# 10_FPGA_misc.net
KiCad netlist of a schematic drawn in Altium Designer
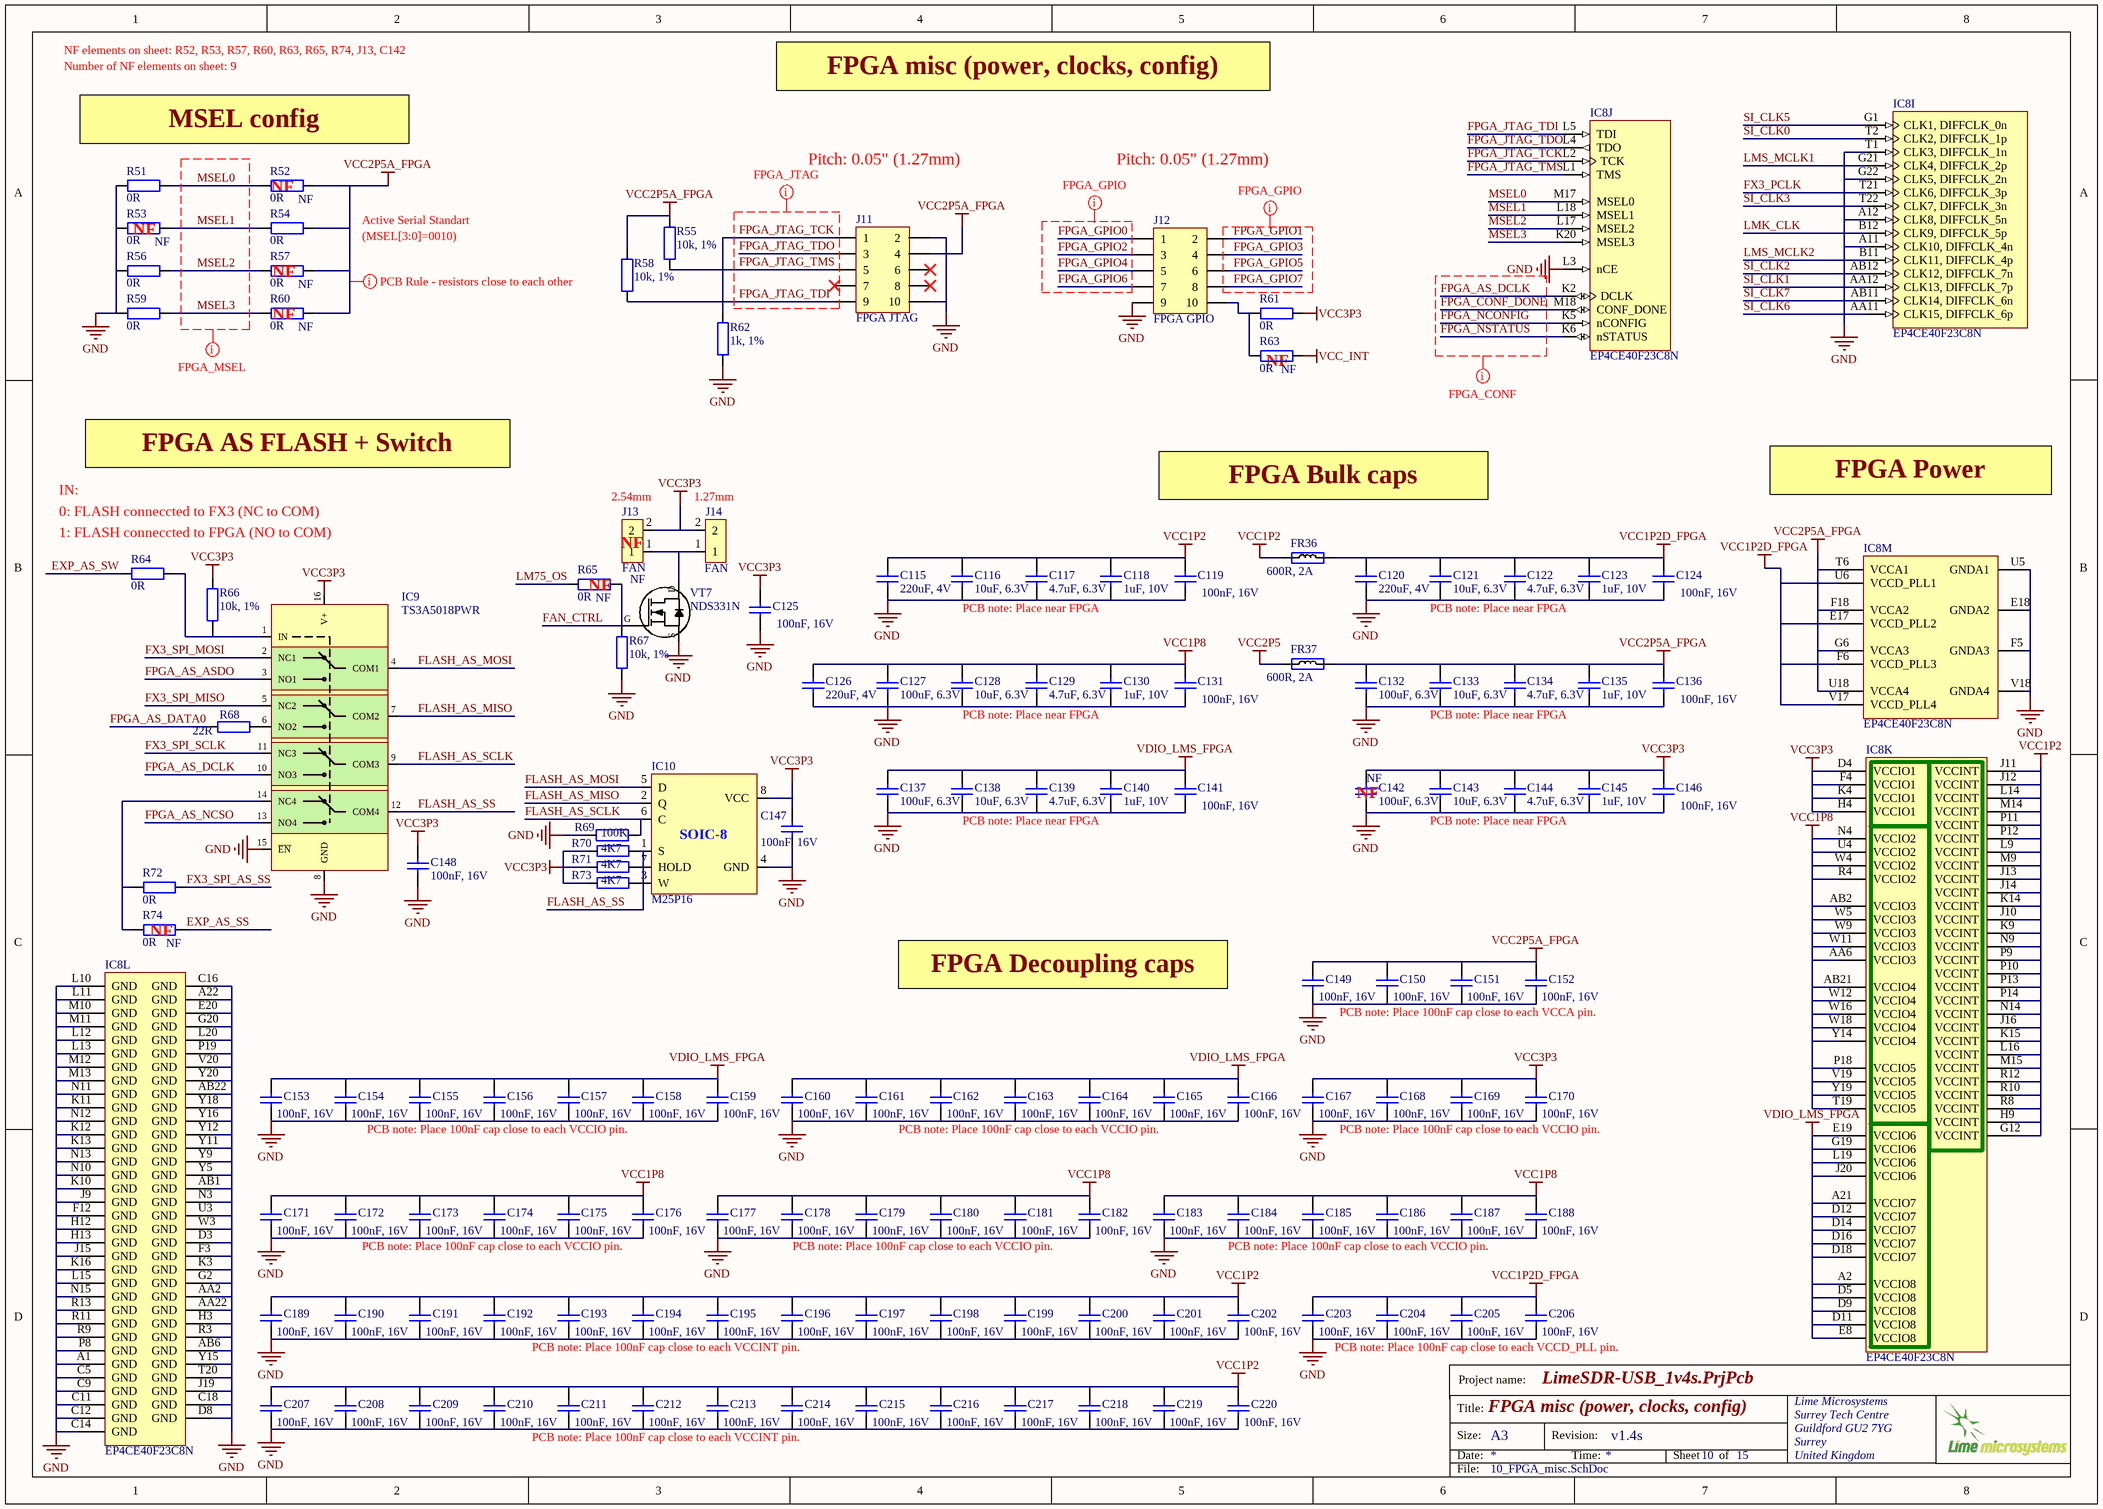
[diagram p0: 10_FPGA_misc.SchDoc]

(export (version "E")
  (design (tool "Eeschema 10.0.6"))
  (components
    (comp (ref "C115")
      (value "220uF, 4V")
      (footprint "CAP1206")
      (fields
        (field (name "MANUFACTURER PART NUMBER") "GRM31CR60G227ME11L")
        (field (name "MANUFACTURER") "Murata Electronics North America")
        (field (name "TOLERANCE") "±20%")
      )
      (libsource (lib "LimeFPGAboard_schLib") (part "Cap_1206"))
    )
    (comp (ref "C116")
      (value "10uF, 6.3V")
      (footprint "CAP0603")
      (fields (field (name "TOLERANCE") "±20%") (field (name "MANUFACTURER") "Yageo"))
      (libsource (lib "LimeFPGAboard_schLib") (part "Cap_0603"))
    )
    (comp (ref "C117")
      (value "4.7uF, 6.3V")
      (footprint "CAP0402")
      (fields
        (field (name "MANUFACTURER") "Murata Electronics North America")
        (field (name "TOLERANCE") "±20%")
        (field (name "MANUFACTURER PART NUMBER") "GRM155R60J475ME87D")
      )
      (libsource (lib "LimeMicroAltiumLib_schLib") (part "Cap_0402"))
    )
    (comp (ref "C118")
      (value "1uF, 10V")
      (footprint "CAP0402")
      (fields (field (name "MANUFACTURER") "TDK"))
      (libsource (lib "LimeMicroAltiumLib_schLib") (part "Cap_0402"))
    )
    (comp (ref "C119")
      (value "100nF, 16V")
      (footprint "CAP0402")
      (fields
        (field (name "TOLERANCE") "10 %")
        (field (name "MANUFACTURER") "Murata Electronics")
        (field (name "MANUFACTURER PART NUMBER") "GRM155R71C104KA88D")
      )
      (libsource (lib "LimeFPGAboard_schLib") (part "Cap_0603"))
    )
    (comp (ref "C120")
      (value "220uF, 4V")
      (footprint "CAP1206")
      (fields
        (field (name "MANUFACTURER PART NUMBER") "GRM31CR60G227ME11L")
        (field (name "MANUFACTURER") "Murata Electronics North America")
        (field (name "TOLERANCE") "±20%")
      )
      (libsource (lib "LimeFPGAboard_schLib") (part "Cap_1206"))
    )
    (comp (ref "C121")
      (value "10uF, 6.3V")
      (footprint "CAP0603")
      (fields (field (name "TOLERANCE") "±20%") (field (name "MANUFACTURER") "Yageo"))
      (libsource (lib "LimeFPGAboard_schLib") (part "Cap_0603"))
    )
    (comp (ref "C122")
      (value "4.7uF, 6.3V")
      (footprint "CAP0402")
      (fields
        (field (name "MANUFACTURER") "Murata Electronics North America")
        (field (name "TOLERANCE") "±20%")
        (field (name "MANUFACTURER PART NUMBER") "GRM155R60J475ME87D")
      )
      (libsource (lib "LimeMicroAltiumLib_schLib") (part "Cap_0402"))
    )
    (comp (ref "C123")
      (value "1uF, 10V")
      (footprint "CAP0402")
      (fields (field (name "MANUFACTURER") "TDK"))
      (libsource (lib "LimeMicroAltiumLib_schLib") (part "Cap_0402"))
    )
    (comp (ref "C124")
      (value "100nF, 16V")
      (footprint "CAP0402")
      (fields
        (field (name "TOLERANCE") "10 %")
        (field (name "MANUFACTURER") "Murata Electronics")
        (field (name "MANUFACTURER PART NUMBER") "GRM155R71C104KA88D")
      )
      (libsource (lib "LimeFPGAboard_schLib") (part "Cap_0603"))
    )
    (comp (ref "C125")
      (value "100nF, 16V")
      (footprint "CAP0402")
      (fields
        (field (name "TOLERANCE") "10 %")
        (field (name "MANUFACTURER") "Murata Electronics")
        (field (name "MANUFACTURER PART NUMBER") "GRM155R71C104KA88D")
      )
      (libsource (lib "LimeFPGAboard_schLib") (part "Cap_0603"))
    )
    (comp (ref "C126")
      (value "220uF, 4V")
      (footprint "CAP1206")
      (fields
        (field (name "MANUFACTURER PART NUMBER") "GRM31CR60G227ME11L")
        (field (name "MANUFACTURER") "Murata Electronics North America")
        (field (name "TOLERANCE") "±20%")
      )
      (libsource (lib "LimeFPGAboard_schLib") (part "Cap_1206"))
    )
    (comp (ref "C127")
      (value "100uF, 6.3V")
      (footprint "CAP1206")
      (fields (field (name "MANUFACTURER") "Murata Electronics North America"))
      (libsource (lib "LimeFPGAboard_schLib") (part "Cap_1206"))
    )
    (comp (ref "C128")
      (value "10uF, 6.3V")
      (footprint "CAP0603")
      (fields (field (name "TOLERANCE") "±20%") (field (name "MANUFACTURER") "Yageo"))
      (libsource (lib "LimeFPGAboard_schLib") (part "Cap_0603"))
    )
    (comp (ref "C129")
      (value "4.7uF, 6.3V")
      (footprint "CAP0402")
      (fields
        (field (name "MANUFACTURER") "Murata Electronics North America")
        (field (name "TOLERANCE") "±20%")
        (field (name "MANUFACTURER PART NUMBER") "GRM155R60J475ME87D")
      )
      (libsource (lib "LimeMicroAltiumLib_schLib") (part "Cap_0402"))
    )
    (comp (ref "C130")
      (value "1uF, 10V")
      (footprint "CAP0402")
      (fields (field (name "MANUFACTURER") "TDK"))
      (libsource (lib "LimeMicroAltiumLib_schLib") (part "Cap_0402"))
    )
    (comp (ref "C131")
      (value "100nF, 16V")
      (footprint "CAP0402")
      (fields
        (field (name "TOLERANCE") "10 %")
        (field (name "MANUFACTURER") "Murata Electronics")
        (field (name "MANUFACTURER PART NUMBER") "GRM155R71C104KA88D")
      )
      (libsource (lib "LimeFPGAboard_schLib") (part "Cap_0603"))
    )
    (comp (ref "C132")
      (value "100uF, 6.3V")
      (footprint "CAP1206")
      (fields (field (name "MANUFACTURER") "Murata Electronics North America"))
      (libsource (lib "LimeFPGAboard_schLib") (part "Cap_1206"))
    )
    (comp (ref "C133")
      (value "10uF, 6.3V")
      (footprint "CAP0603")
      (fields (field (name "TOLERANCE") "±20%") (field (name "MANUFACTURER") "Yageo"))
      (libsource (lib "LimeFPGAboard_schLib") (part "Cap_0603"))
    )
    (comp (ref "C134")
      (value "4.7uF, 6.3V")
      (footprint "CAP0402")
      (fields
        (field (name "MANUFACTURER") "Murata Electronics North America")
        (field (name "TOLERANCE") "±20%")
        (field (name "MANUFACTURER PART NUMBER") "GRM155R60J475ME87D")
      )
      (libsource (lib "LimeMicroAltiumLib_schLib") (part "Cap_0402"))
    )
    (comp (ref "C135")
      (value "1uF, 10V")
      (footprint "CAP0402")
      (fields (field (name "MANUFACTURER") "TDK"))
      (libsource (lib "LimeMicroAltiumLib_schLib") (part "Cap_0402"))
    )
    (comp (ref "C136")
      (value "100nF, 16V")
      (footprint "CAP0402")
      (fields
        (field (name "TOLERANCE") "10 %")
        (field (name "MANUFACTURER") "Murata Electronics")
        (field (name "MANUFACTURER PART NUMBER") "GRM155R71C104KA88D")
      )
      (libsource (lib "LimeFPGAboard_schLib") (part "Cap_0603"))
    )
    (comp (ref "C137")
      (value "100uF, 6.3V")
      (footprint "CAP1206")
      (fields (field (name "MANUFACTURER") "Murata Electronics North America"))
      (libsource (lib "LimeFPGAboard_schLib") (part "Cap_1206"))
    )
    (comp (ref "C138")
      (value "10uF, 6.3V")
      (footprint "CAP0603")
      (fields (field (name "TOLERANCE") "±20%") (field (name "MANUFACTURER") "Yageo"))
      (libsource (lib "LimeFPGAboard_schLib") (part "Cap_0603"))
    )
    (comp (ref "C139")
      (value "4.7uF, 6.3V")
      (footprint "CAP0402")
      (fields
        (field (name "MANUFACTURER") "Murata Electronics North America")
        (field (name "TOLERANCE") "±20%")
        (field (name "MANUFACTURER PART NUMBER") "GRM155R60J475ME87D")
      )
      (libsource (lib "LimeMicroAltiumLib_schLib") (part "Cap_0402"))
    )
    (comp (ref "C140")
      (value "1uF, 10V")
      (footprint "CAP0402")
      (fields (field (name "MANUFACTURER") "TDK"))
      (libsource (lib "LimeMicroAltiumLib_schLib") (part "Cap_0402"))
    )
    (comp (ref "C141")
      (value "100nF, 16V")
      (footprint "CAP0402")
      (fields
        (field (name "TOLERANCE") "10 %")
        (field (name "MANUFACTURER") "Murata Electronics")
        (field (name "MANUFACTURER PART NUMBER") "GRM155R71C104KA88D")
      )
      (libsource (lib "LimeFPGAboard_schLib") (part "Cap_0603"))
    )
    (comp (ref "C142")
      (value "100uF, 6.3V")
      (footprint "CAP1206")
      (fields
        (field (name "MANUFACTURER") "Murata Electronics North America")
        (field (name "ASSEMBLY INFO") "NF")
      )
      (libsource (lib "LimeFPGAboard_schLib") (part "Cap_1206"))
    )
    (comp (ref "C143")
      (value "10uF, 6.3V")
      (footprint "CAP0603")
      (fields (field (name "TOLERANCE") "±20%") (field (name "MANUFACTURER") "Yageo"))
      (libsource (lib "LimeFPGAboard_schLib") (part "Cap_0603"))
    )
    (comp (ref "C144")
      (value "4.7uF, 6.3V")
      (footprint "CAP0402")
      (fields
        (field (name "MANUFACTURER") "Murata Electronics North America")
        (field (name "TOLERANCE") "±20%")
        (field (name "MANUFACTURER PART NUMBER") "GRM155R60J475ME87D")
      )
      (libsource (lib "LimeMicroAltiumLib_schLib") (part "Cap_0402"))
    )
    (comp (ref "C145")
      (value "1uF, 10V")
      (footprint "CAP0402")
      (fields (field (name "MANUFACTURER") "TDK"))
      (libsource (lib "LimeMicroAltiumLib_schLib") (part "Cap_0402"))
    )
    (comp (ref "C146")
      (value "100nF, 16V")
      (footprint "CAP0402")
      (fields
        (field (name "TOLERANCE") "10 %")
        (field (name "MANUFACTURER") "Murata Electronics")
        (field (name "MANUFACTURER PART NUMBER") "GRM155R71C104KA88D")
      )
      (libsource (lib "LimeFPGAboard_schLib") (part "Cap_0603"))
    )
    (comp (ref "C147")
      (value "100nF, 16V")
      (footprint "CAP0402")
      (fields
        (field (name "TOLERANCE") "10 %")
        (field (name "MANUFACTURER") "Murata Electronics")
        (field (name "MANUFACTURER PART NUMBER") "GRM155R71C104KA88D")
      )
      (libsource (lib "LimeFPGAboard_schLib") (part "Cap_0603"))
    )
    (comp (ref "C148")
      (value "100nF, 16V")
      (footprint "CAP0402")
      (fields
        (field (name "TOLERANCE") "10 %")
        (field (name "MANUFACTURER") "Murata Electronics")
        (field (name "MANUFACTURER PART NUMBER") "GRM155R71C104KA88D")
      )
      (libsource (lib "LimeFPGAboard_schLib") (part "Cap_0603"))
    )
    (comp (ref "C149")
      (value "100nF, 16V")
      (footprint "CAP0402")
      (fields
        (field (name "TOLERANCE") "10 %")
        (field (name "MANUFACTURER") "Murata Electronics")
        (field (name "MANUFACTURER PART NUMBER") "GRM155R71C104KA88D")
      )
      (libsource (lib "LimeFPGAboard_schLib") (part "Cap_0603"))
    )
    (comp (ref "C150")
      (value "100nF, 16V")
      (footprint "CAP0402")
      (fields
        (field (name "TOLERANCE") "10 %")
        (field (name "MANUFACTURER") "Murata Electronics")
        (field (name "MANUFACTURER PART NUMBER") "GRM155R71C104KA88D")
      )
      (libsource (lib "LimeFPGAboard_schLib") (part "Cap_0603"))
    )
    (comp (ref "C151")
      (value "100nF, 16V")
      (footprint "CAP0402")
      (fields
        (field (name "TOLERANCE") "10 %")
        (field (name "MANUFACTURER") "Murata Electronics")
        (field (name "MANUFACTURER PART NUMBER") "GRM155R71C104KA88D")
      )
      (libsource (lib "LimeFPGAboard_schLib") (part "Cap_0603"))
    )
    (comp (ref "C152")
      (value "100nF, 16V")
      (footprint "CAP0402")
      (fields
        (field (name "TOLERANCE") "10 %")
        (field (name "MANUFACTURER") "Murata Electronics")
        (field (name "MANUFACTURER PART NUMBER") "GRM155R71C104KA88D")
      )
      (libsource (lib "LimeFPGAboard_schLib") (part "Cap_0603"))
    )
    (comp (ref "C153")
      (value "100nF, 16V")
      (footprint "CAP0402")
      (fields
        (field (name "TOLERANCE") "10 %")
        (field (name "MANUFACTURER") "Murata Electronics")
        (field (name "MANUFACTURER PART NUMBER") "GRM155R71C104KA88D")
      )
      (libsource (lib "LimeFPGAboard_schLib") (part "Cap_0603"))
    )
    (comp (ref "C154")
      (value "100nF, 16V")
      (footprint "CAP0402")
      (fields
        (field (name "TOLERANCE") "10 %")
        (field (name "MANUFACTURER") "Murata Electronics")
        (field (name "MANUFACTURER PART NUMBER") "GRM155R71C104KA88D")
      )
      (libsource (lib "LimeFPGAboard_schLib") (part "Cap_0603"))
    )
    (comp (ref "C155")
      (value "100nF, 16V")
      (footprint "CAP0402")
      (fields
        (field (name "TOLERANCE") "10 %")
        (field (name "MANUFACTURER") "Murata Electronics")
        (field (name "MANUFACTURER PART NUMBER") "GRM155R71C104KA88D")
      )
      (libsource (lib "LimeFPGAboard_schLib") (part "Cap_0603"))
    )
    (comp (ref "C156")
      (value "100nF, 16V")
      (footprint "CAP0402")
      (fields
        (field (name "TOLERANCE") "10 %")
        (field (name "MANUFACTURER") "Murata Electronics")
        (field (name "MANUFACTURER PART NUMBER") "GRM155R71C104KA88D")
      )
      (libsource (lib "LimeFPGAboard_schLib") (part "Cap_0603"))
    )
    (comp (ref "C157")
      (value "100nF, 16V")
      (footprint "CAP0402")
      (fields
        (field (name "TOLERANCE") "10 %")
        (field (name "MANUFACTURER") "Murata Electronics")
        (field (name "MANUFACTURER PART NUMBER") "GRM155R71C104KA88D")
      )
      (libsource (lib "LimeFPGAboard_schLib") (part "Cap_0603"))
    )
    (comp (ref "C158")
      (value "100nF, 16V")
      (footprint "CAP0402")
      (fields
        (field (name "TOLERANCE") "10 %")
        (field (name "MANUFACTURER") "Murata Electronics")
        (field (name "MANUFACTURER PART NUMBER") "GRM155R71C104KA88D")
      )
      (libsource (lib "LimeFPGAboard_schLib") (part "Cap_0603"))
    )
    (comp (ref "C159")
      (value "100nF, 16V")
      (footprint "CAP0402")
      (fields
        (field (name "TOLERANCE") "10 %")
        (field (name "MANUFACTURER") "Murata Electronics")
        (field (name "MANUFACTURER PART NUMBER") "GRM155R71C104KA88D")
      )
      (libsource (lib "LimeFPGAboard_schLib") (part "Cap_0603"))
    )
    (comp (ref "C160")
      (value "100nF, 16V")
      (footprint "CAP0402")
      (fields
        (field (name "TOLERANCE") "10 %")
        (field (name "MANUFACTURER") "Murata Electronics")
        (field (name "MANUFACTURER PART NUMBER") "GRM155R71C104KA88D")
      )
      (libsource (lib "LimeFPGAboard_schLib") (part "Cap_0603"))
    )
    (comp (ref "C161")
      (value "100nF, 16V")
      (footprint "CAP0402")
      (fields
        (field (name "TOLERANCE") "10 %")
        (field (name "MANUFACTURER") "Murata Electronics")
        (field (name "MANUFACTURER PART NUMBER") "GRM155R71C104KA88D")
      )
      (libsource (lib "LimeFPGAboard_schLib") (part "Cap_0603"))
    )
    (comp (ref "C162")
      (value "100nF, 16V")
      (footprint "CAP0402")
      (fields
        (field (name "TOLERANCE") "10 %")
        (field (name "MANUFACTURER") "Murata Electronics")
        (field (name "MANUFACTURER PART NUMBER") "GRM155R71C104KA88D")
      )
      (libsource (lib "LimeFPGAboard_schLib") (part "Cap_0603"))
    )
    (comp (ref "C163")
      (value "100nF, 16V")
      (footprint "CAP0402")
      (fields
        (field (name "TOLERANCE") "10 %")
        (field (name "MANUFACTURER") "Murata Electronics")
        (field (name "MANUFACTURER PART NUMBER") "GRM155R71C104KA88D")
      )
      (libsource (lib "LimeFPGAboard_schLib") (part "Cap_0603"))
    )
    (comp (ref "C164")
      (value "100nF, 16V")
      (footprint "CAP0402")
      (fields
        (field (name "TOLERANCE") "10 %")
        (field (name "MANUFACTURER") "Murata Electronics")
        (field (name "MANUFACTURER PART NUMBER") "GRM155R71C104KA88D")
      )
      (libsource (lib "LimeFPGAboard_schLib") (part "Cap_0603"))
    )
    (comp (ref "C165")
      (value "100nF, 16V")
      (footprint "CAP0402")
      (fields
        (field (name "TOLERANCE") "10 %")
        (field (name "MANUFACTURER") "Murata Electronics")
        (field (name "MANUFACTURER PART NUMBER") "GRM155R71C104KA88D")
      )
      (libsource (lib "LimeFPGAboard_schLib") (part "Cap_0603"))
    )
    (comp (ref "C166")
      (value "100nF, 16V")
      (footprint "CAP0402")
      (fields
        (field (name "TOLERANCE") "10 %")
        (field (name "MANUFACTURER") "Murata Electronics")
        (field (name "MANUFACTURER PART NUMBER") "GRM155R71C104KA88D")
      )
      (libsource (lib "LimeFPGAboard_schLib") (part "Cap_0603"))
    )
    (comp (ref "C167")
      (value "100nF, 16V")
      (footprint "CAP0402")
      (fields
        (field (name "TOLERANCE") "10 %")
        (field (name "MANUFACTURER") "Murata Electronics")
        (field (name "MANUFACTURER PART NUMBER") "GRM155R71C104KA88D")
      )
      (libsource (lib "LimeFPGAboard_schLib") (part "Cap_0603"))
    )
    (comp (ref "C168")
      (value "100nF, 16V")
      (footprint "CAP0402")
      (fields
        (field (name "TOLERANCE") "10 %")
        (field (name "MANUFACTURER") "Murata Electronics")
        (field (name "MANUFACTURER PART NUMBER") "GRM155R71C104KA88D")
      )
      (libsource (lib "LimeFPGAboard_schLib") (part "Cap_0603"))
    )
    (comp (ref "C169")
      (value "100nF, 16V")
      (footprint "CAP0402")
      (fields
        (field (name "TOLERANCE") "10 %")
        (field (name "MANUFACTURER") "Murata Electronics")
        (field (name "MANUFACTURER PART NUMBER") "GRM155R71C104KA88D")
      )
      (libsource (lib "LimeFPGAboard_schLib") (part "Cap_0603"))
    )
    (comp (ref "C170")
      (value "100nF, 16V")
      (footprint "CAP0402")
      (fields
        (field (name "TOLERANCE") "10 %")
        (field (name "MANUFACTURER") "Murata Electronics")
        (field (name "MANUFACTURER PART NUMBER") "GRM155R71C104KA88D")
      )
      (libsource (lib "LimeFPGAboard_schLib") (part "Cap_0603"))
    )
    (comp (ref "C171")
      (value "100nF, 16V")
      (footprint "CAP0402")
      (fields
        (field (name "TOLERANCE") "10 %")
        (field (name "MANUFACTURER") "Murata Electronics")
        (field (name "MANUFACTURER PART NUMBER") "GRM155R71C104KA88D")
      )
      (libsource (lib "LimeFPGAboard_schLib") (part "Cap_0603"))
    )
    (comp (ref "C172")
      (value "100nF, 16V")
      (footprint "CAP0402")
      (fields
        (field (name "TOLERANCE") "10 %")
        (field (name "MANUFACTURER") "Murata Electronics")
        (field (name "MANUFACTURER PART NUMBER") "GRM155R71C104KA88D")
      )
      (libsource (lib "LimeFPGAboard_schLib") (part "Cap_0603"))
    )
    (comp (ref "C173")
      (value "100nF, 16V")
      (footprint "CAP0402")
      (fields
        (field (name "TOLERANCE") "10 %")
        (field (name "MANUFACTURER") "Murata Electronics")
        (field (name "MANUFACTURER PART NUMBER") "GRM155R71C104KA88D")
      )
      (libsource (lib "LimeFPGAboard_schLib") (part "Cap_0603"))
    )
    (comp (ref "C174")
      (value "100nF, 16V")
      (footprint "CAP0402")
      (fields
        (field (name "TOLERANCE") "10 %")
        (field (name "MANUFACTURER") "Murata Electronics")
        (field (name "MANUFACTURER PART NUMBER") "GRM155R71C104KA88D")
      )
      (libsource (lib "LimeFPGAboard_schLib") (part "Cap_0603"))
    )
    (comp (ref "C175")
      (value "100nF, 16V")
      (footprint "CAP0402")
      (fields
        (field (name "TOLERANCE") "10 %")
        (field (name "MANUFACTURER") "Murata Electronics")
        (field (name "MANUFACTURER PART NUMBER") "GRM155R71C104KA88D")
      )
      (libsource (lib "LimeFPGAboard_schLib") (part "Cap_0603"))
    )
    (comp (ref "C176")
      (value "100nF, 16V")
      (footprint "CAP0402")
      (fields
        (field (name "TOLERANCE") "10 %")
        (field (name "MANUFACTURER") "Murata Electronics")
        (field (name "MANUFACTURER PART NUMBER") "GRM155R71C104KA88D")
      )
      (libsource (lib "LimeFPGAboard_schLib") (part "Cap_0603"))
    )
    (comp (ref "C177")
      (value "100nF, 16V")
      (footprint "CAP0402")
      (fields
        (field (name "TOLERANCE") "10 %")
        (field (name "MANUFACTURER") "Murata Electronics")
        (field (name "MANUFACTURER PART NUMBER") "GRM155R71C104KA88D")
      )
      (libsource (lib "LimeFPGAboard_schLib") (part "Cap_0603"))
    )
    (comp (ref "C178")
      (value "100nF, 16V")
      (footprint "CAP0402")
      (fields
        (field (name "TOLERANCE") "10 %")
        (field (name "MANUFACTURER") "Murata Electronics")
        (field (name "MANUFACTURER PART NUMBER") "GRM155R71C104KA88D")
      )
      (libsource (lib "LimeFPGAboard_schLib") (part "Cap_0603"))
    )
    (comp (ref "C179")
      (value "100nF, 16V")
      (footprint "CAP0402")
      (fields
        (field (name "TOLERANCE") "10 %")
        (field (name "MANUFACTURER") "Murata Electronics")
        (field (name "MANUFACTURER PART NUMBER") "GRM155R71C104KA88D")
      )
      (libsource (lib "LimeFPGAboard_schLib") (part "Cap_0603"))
    )
    (comp (ref "C180")
      (value "100nF, 16V")
      (footprint "CAP0402")
      (fields
        (field (name "TOLERANCE") "10 %")
        (field (name "MANUFACTURER") "Murata Electronics")
        (field (name "MANUFACTURER PART NUMBER") "GRM155R71C104KA88D")
      )
      (libsource (lib "LimeFPGAboard_schLib") (part "Cap_0603"))
    )
    (comp (ref "C181")
      (value "100nF, 16V")
      (footprint "CAP0402")
      (fields
        (field (name "TOLERANCE") "10 %")
        (field (name "MANUFACTURER") "Murata Electronics")
        (field (name "MANUFACTURER PART NUMBER") "GRM155R71C104KA88D")
      )
      (libsource (lib "LimeFPGAboard_schLib") (part "Cap_0603"))
    )
    (comp (ref "C182")
      (value "100nF, 16V")
      (footprint "CAP0402")
      (fields
        (field (name "TOLERANCE") "10 %")
        (field (name "MANUFACTURER") "Murata Electronics")
        (field (name "MANUFACTURER PART NUMBER") "GRM155R71C104KA88D")
      )
      (libsource (lib "LimeFPGAboard_schLib") (part "Cap_0603"))
    )
    (comp (ref "C183")
      (value "100nF, 16V")
      (footprint "CAP0402")
      (fields
        (field (name "TOLERANCE") "10 %")
        (field (name "MANUFACTURER") "Murata Electronics")
        (field (name "MANUFACTURER PART NUMBER") "GRM155R71C104KA88D")
      )
      (libsource (lib "LimeFPGAboard_schLib") (part "Cap_0603"))
    )
    (comp (ref "C184")
      (value "100nF, 16V")
      (footprint "CAP0402")
      (fields
        (field (name "TOLERANCE") "10 %")
        (field (name "MANUFACTURER") "Murata Electronics")
        (field (name "MANUFACTURER PART NUMBER") "GRM155R71C104KA88D")
      )
      (libsource (lib "LimeFPGAboard_schLib") (part "Cap_0603"))
    )
    (comp (ref "C185")
      (value "100nF, 16V")
      (footprint "CAP0402")
      (fields
        (field (name "TOLERANCE") "10 %")
        (field (name "MANUFACTURER") "Murata Electronics")
        (field (name "MANUFACTURER PART NUMBER") "GRM155R71C104KA88D")
      )
      (libsource (lib "LimeFPGAboard_schLib") (part "Cap_0603"))
    )
    (comp (ref "C186")
      (value "100nF, 16V")
      (footprint "CAP0402")
      (fields
        (field (name "TOLERANCE") "10 %")
        (field (name "MANUFACTURER") "Murata Electronics")
        (field (name "MANUFACTURER PART NUMBER") "GRM155R71C104KA88D")
      )
      (libsource (lib "LimeFPGAboard_schLib") (part "Cap_0603"))
    )
    (comp (ref "C187")
      (value "100nF, 16V")
      (footprint "CAP0402")
      (fields
        (field (name "TOLERANCE") "10 %")
        (field (name "MANUFACTURER") "Murata Electronics")
        (field (name "MANUFACTURER PART NUMBER") "GRM155R71C104KA88D")
      )
      (libsource (lib "LimeFPGAboard_schLib") (part "Cap_0603"))
    )
    (comp (ref "C188")
      (value "100nF, 16V")
      (footprint "CAP0402")
      (fields
        (field (name "TOLERANCE") "10 %")
        (field (name "MANUFACTURER") "Murata Electronics")
        (field (name "MANUFACTURER PART NUMBER") "GRM155R71C104KA88D")
      )
      (libsource (lib "LimeFPGAboard_schLib") (part "Cap_0603"))
    )
    (comp (ref "C189")
      (value "100nF, 16V")
      (footprint "CAP0402")
      (fields
        (field (name "TOLERANCE") "10 %")
        (field (name "MANUFACTURER") "Murata Electronics")
        (field (name "MANUFACTURER PART NUMBER") "GRM155R71C104KA88D")
      )
      (libsource (lib "LimeFPGAboard_schLib") (part "Cap_0603"))
    )
    (comp (ref "C190")
      (value "100nF, 16V")
      (footprint "CAP0402")
      (fields
        (field (name "TOLERANCE") "10 %")
        (field (name "MANUFACTURER") "Murata Electronics")
        (field (name "MANUFACTURER PART NUMBER") "GRM155R71C104KA88D")
      )
      (libsource (lib "LimeFPGAboard_schLib") (part "Cap_0603"))
    )
    (comp (ref "C191")
      (value "100nF, 16V")
      (footprint "CAP0402")
      (fields
        (field (name "TOLERANCE") "10 %")
        (field (name "MANUFACTURER") "Murata Electronics")
        (field (name "MANUFACTURER PART NUMBER") "GRM155R71C104KA88D")
      )
      (libsource (lib "LimeFPGAboard_schLib") (part "Cap_0603"))
    )
    (comp (ref "C192")
      (value "100nF, 16V")
      (footprint "CAP0402")
      (fields
        (field (name "TOLERANCE") "10 %")
        (field (name "MANUFACTURER") "Murata Electronics")
        (field (name "MANUFACTURER PART NUMBER") "GRM155R71C104KA88D")
      )
      (libsource (lib "LimeFPGAboard_schLib") (part "Cap_0603"))
    )
    (comp (ref "C193")
      (value "100nF, 16V")
      (footprint "CAP0402")
      (fields
        (field (name "TOLERANCE") "10 %")
        (field (name "MANUFACTURER") "Murata Electronics")
        (field (name "MANUFACTURER PART NUMBER") "GRM155R71C104KA88D")
      )
      (libsource (lib "LimeFPGAboard_schLib") (part "Cap_0603"))
    )
    (comp (ref "C194")
      (value "100nF, 16V")
      (footprint "CAP0402")
      (fields
        (field (name "TOLERANCE") "10 %")
        (field (name "MANUFACTURER") "Murata Electronics")
        (field (name "MANUFACTURER PART NUMBER") "GRM155R71C104KA88D")
      )
      (libsource (lib "LimeFPGAboard_schLib") (part "Cap_0603"))
    )
    (comp (ref "C195")
      (value "100nF, 16V")
      (footprint "CAP0402")
      (fields
        (field (name "TOLERANCE") "10 %")
        (field (name "MANUFACTURER") "Murata Electronics")
        (field (name "MANUFACTURER PART NUMBER") "GRM155R71C104KA88D")
      )
      (libsource (lib "LimeFPGAboard_schLib") (part "Cap_0603"))
    )
    (comp (ref "C196")
      (value "100nF, 16V")
      (footprint "CAP0402")
      (fields
        (field (name "TOLERANCE") "10 %")
        (field (name "MANUFACTURER") "Murata Electronics")
        (field (name "MANUFACTURER PART NUMBER") "GRM155R71C104KA88D")
      )
      (libsource (lib "LimeFPGAboard_schLib") (part "Cap_0603"))
    )
    (comp (ref "C197")
      (value "100nF, 16V")
      (footprint "CAP0402")
      (fields
        (field (name "TOLERANCE") "10 %")
        (field (name "MANUFACTURER") "Murata Electronics")
        (field (name "MANUFACTURER PART NUMBER") "GRM155R71C104KA88D")
      )
      (libsource (lib "LimeFPGAboard_schLib") (part "Cap_0603"))
    )
    (comp (ref "C198")
      (value "100nF, 16V")
      (footprint "CAP0402")
      (fields
        (field (name "TOLERANCE") "10 %")
        (field (name "MANUFACTURER") "Murata Electronics")
        (field (name "MANUFACTURER PART NUMBER") "GRM155R71C104KA88D")
      )
      (libsource (lib "LimeFPGAboard_schLib") (part "Cap_0603"))
    )
    (comp (ref "C199")
      (value "100nF, 16V")
      (footprint "CAP0402")
      (fields
        (field (name "TOLERANCE") "10 %")
        (field (name "MANUFACTURER") "Murata Electronics")
        (field (name "MANUFACTURER PART NUMBER") "GRM155R71C104KA88D")
      )
      (libsource (lib "LimeFPGAboard_schLib") (part "Cap_0603"))
    )
    (comp (ref "C200")
      (value "100nF, 16V")
      (footprint "CAP0402")
      (fields
        (field (name "TOLERANCE") "10 %")
        (field (name "MANUFACTURER") "Murata Electronics")
        (field (name "MANUFACTURER PART NUMBER") "GRM155R71C104KA88D")
      )
      (libsource (lib "LimeFPGAboard_schLib") (part "Cap_0603"))
    )
    (comp (ref "C201")
      (value "100nF, 16V")
      (footprint "CAP0402")
      (fields
        (field (name "TOLERANCE") "10 %")
        (field (name "MANUFACTURER") "Murata Electronics")
        (field (name "MANUFACTURER PART NUMBER") "GRM155R71C104KA88D")
      )
      (libsource (lib "LimeFPGAboard_schLib") (part "Cap_0603"))
    )
    (comp (ref "C202")
      (value "100nF, 16V")
      (footprint "CAP0402")
      (fields
        (field (name "TOLERANCE") "10 %")
        (field (name "MANUFACTURER") "Murata Electronics")
        (field (name "MANUFACTURER PART NUMBER") "GRM155R71C104KA88D")
      )
      (libsource (lib "LimeFPGAboard_schLib") (part "Cap_0603"))
    )
    (comp (ref "C203")
      (value "100nF, 16V")
      (footprint "CAP0402")
      (fields
        (field (name "TOLERANCE") "10 %")
        (field (name "MANUFACTURER") "Murata Electronics")
        (field (name "MANUFACTURER PART NUMBER") "GRM155R71C104KA88D")
      )
      (libsource (lib "LimeFPGAboard_schLib") (part "Cap_0603"))
    )
    (comp (ref "C204")
      (value "100nF, 16V")
      (footprint "CAP0402")
      (fields
        (field (name "TOLERANCE") "10 %")
        (field (name "MANUFACTURER") "Murata Electronics")
        (field (name "MANUFACTURER PART NUMBER") "GRM155R71C104KA88D")
      )
      (libsource (lib "LimeFPGAboard_schLib") (part "Cap_0603"))
    )
    (comp (ref "C205")
      (value "100nF, 16V")
      (footprint "CAP0402")
      (fields
        (field (name "TOLERANCE") "10 %")
        (field (name "MANUFACTURER") "Murata Electronics")
        (field (name "MANUFACTURER PART NUMBER") "GRM155R71C104KA88D")
      )
      (libsource (lib "LimeFPGAboard_schLib") (part "Cap_0603"))
    )
    (comp (ref "C206")
      (value "100nF, 16V")
      (footprint "CAP0402")
      (fields
        (field (name "TOLERANCE") "10 %")
        (field (name "MANUFACTURER") "Murata Electronics")
        (field (name "MANUFACTURER PART NUMBER") "GRM155R71C104KA88D")
      )
      (libsource (lib "LimeFPGAboard_schLib") (part "Cap_0603"))
    )
    (comp (ref "C207")
      (value "100nF, 16V")
      (footprint "CAP0402")
      (fields
        (field (name "TOLERANCE") "10 %")
        (field (name "MANUFACTURER") "Murata Electronics")
        (field (name "MANUFACTURER PART NUMBER") "GRM155R71C104KA88D")
      )
      (libsource (lib "LimeFPGAboard_schLib") (part "Cap_0603"))
    )
    (comp (ref "C208")
      (value "100nF, 16V")
      (footprint "CAP0402")
      (fields
        (field (name "TOLERANCE") "10 %")
        (field (name "MANUFACTURER") "Murata Electronics")
        (field (name "MANUFACTURER PART NUMBER") "GRM155R71C104KA88D")
      )
      (libsource (lib "LimeFPGAboard_schLib") (part "Cap_0603"))
    )
    (comp (ref "C209")
      (value "100nF, 16V")
      (footprint "CAP0402")
      (fields
        (field (name "TOLERANCE") "10 %")
        (field (name "MANUFACTURER") "Murata Electronics")
        (field (name "MANUFACTURER PART NUMBER") "GRM155R71C104KA88D")
      )
      (libsource (lib "LimeFPGAboard_schLib") (part "Cap_0603"))
    )
    (comp (ref "C210")
      (value "100nF, 16V")
      (footprint "CAP0402")
      (fields
        (field (name "TOLERANCE") "10 %")
        (field (name "MANUFACTURER") "Murata Electronics")
        (field (name "MANUFACTURER PART NUMBER") "GRM155R71C104KA88D")
      )
      (libsource (lib "LimeFPGAboard_schLib") (part "Cap_0603"))
    )
    (comp (ref "C211")
      (value "100nF, 16V")
      (footprint "CAP0402")
      (fields
        (field (name "TOLERANCE") "10 %")
        (field (name "MANUFACTURER") "Murata Electronics")
        (field (name "MANUFACTURER PART NUMBER") "GRM155R71C104KA88D")
      )
      (libsource (lib "LimeFPGAboard_schLib") (part "Cap_0603"))
    )
    (comp (ref "C212")
      (value "100nF, 16V")
      (footprint "CAP0402")
      (fields
        (field (name "TOLERANCE") "10 %")
        (field (name "MANUFACTURER") "Murata Electronics")
        (field (name "MANUFACTURER PART NUMBER") "GRM155R71C104KA88D")
      )
      (libsource (lib "LimeFPGAboard_schLib") (part "Cap_0603"))
    )
    (comp (ref "C213")
      (value "100nF, 16V")
      (footprint "CAP0402")
      (fields
        (field (name "TOLERANCE") "10 %")
        (field (name "MANUFACTURER") "Murata Electronics")
        (field (name "MANUFACTURER PART NUMBER") "GRM155R71C104KA88D")
      )
      (libsource (lib "LimeFPGAboard_schLib") (part "Cap_0603"))
    )
    (comp (ref "C214")
      (value "100nF, 16V")
      (footprint "CAP0402")
      (fields
        (field (name "TOLERANCE") "10 %")
        (field (name "MANUFACTURER") "Murata Electronics")
        (field (name "MANUFACTURER PART NUMBER") "GRM155R71C104KA88D")
      )
      (libsource (lib "LimeFPGAboard_schLib") (part "Cap_0603"))
    )
    (comp (ref "C215")
      (value "100nF, 16V")
      (footprint "CAP0402")
      (fields
        (field (name "TOLERANCE") "10 %")
        (field (name "MANUFACTURER") "Murata Electronics")
        (field (name "MANUFACTURER PART NUMBER") "GRM155R71C104KA88D")
      )
      (libsource (lib "LimeFPGAboard_schLib") (part "Cap_0603"))
    )
    (comp (ref "C216")
      (value "100nF, 16V")
      (footprint "CAP0402")
      (fields
        (field (name "TOLERANCE") "10 %")
        (field (name "MANUFACTURER") "Murata Electronics")
        (field (name "MANUFACTURER PART NUMBER") "GRM155R71C104KA88D")
      )
      (libsource (lib "LimeFPGAboard_schLib") (part "Cap_0603"))
    )
    (comp (ref "C217")
      (value "100nF, 16V")
      (footprint "CAP0402")
      (fields
        (field (name "TOLERANCE") "10 %")
        (field (name "MANUFACTURER") "Murata Electronics")
        (field (name "MANUFACTURER PART NUMBER") "GRM155R71C104KA88D")
      )
      (libsource (lib "LimeFPGAboard_schLib") (part "Cap_0603"))
    )
    (comp (ref "C218")
      (value "100nF, 16V")
      (footprint "CAP0402")
      (fields
        (field (name "TOLERANCE") "10 %")
        (field (name "MANUFACTURER") "Murata Electronics")
        (field (name "MANUFACTURER PART NUMBER") "GRM155R71C104KA88D")
      )
      (libsource (lib "LimeFPGAboard_schLib") (part "Cap_0603"))
    )
    (comp (ref "C219")
      (value "100nF, 16V")
      (footprint "CAP0402")
      (fields
        (field (name "TOLERANCE") "10 %")
        (field (name "MANUFACTURER") "Murata Electronics")
        (field (name "MANUFACTURER PART NUMBER") "GRM155R71C104KA88D")
      )
      (libsource (lib "LimeFPGAboard_schLib") (part "Cap_0603"))
    )
    (comp (ref "C220")
      (value "100nF, 16V")
      (footprint "CAP0402")
      (fields
        (field (name "TOLERANCE") "10 %")
        (field (name "MANUFACTURER") "Murata Electronics")
        (field (name "MANUFACTURER PART NUMBER") "GRM155R71C104KA88D")
      )
      (libsource (lib "LimeFPGAboard_schLib") (part "Cap_0603"))
    )
    (comp (ref "FR36")
      (value "600R, 2A")
      (footprint "RES0805")
      (fields (field (name "MANUFACTURER") "TDK Corporation"))
      (libsource (lib "LimeMicroAltiumLib_schLib") (part "Ferrite"))
    )
    (comp (ref "FR37")
      (value "600R, 2A")
      (footprint "RES0805")
      (fields (field (name "MANUFACTURER") "TDK Corporation"))
      (libsource (lib "LimeMicroAltiumLib_schLib") (part "Ferrite"))
    )
    (comp (ref "IC8")
      (value "EP4CE40F23C8N")
      (footprint "FBGA484_A-240")
      (description "IC FPGA 328 I/O 484FBGA")
      (fields (field (name "MANUFACTURER") "Altera"))
      (libsource (lib "LimeMicroAltiumLib_schLib") (part "EP4CE40F23C7N"))
    )
    (comp (ref "IC9")
      (value "TS3A5018PWR")
      (footprint "TS3A5018PWR")
      (fields (field (name "MANUFACTURER") "TEXAS INSTRUMENTS"))
      (libsource (lib "LimeFPGAboard_schLib") (part "TS3A5018PWR"))
    )
    (comp (ref "IC10")
      (value "M25P16")
      (footprint "M25P40-VMN6TPB_SO8N")
      (fields (field (name "MANUFACTURER") "Micron Technology Inc."))
      (libsource (lib "LimeFPGAboard_schLib") (part "M25P40"))
    )
    (comp (ref "J11")
      (value "FPGA JTAG")
      (footprint "SWD_10_pin")
      (description "Header, 5-Pin, Dual row")
      (fields (field (name "MANUFACTURER") "Harwin Inc"))
      (libsource (lib "LimeMicroAltiumLib_schLib") (part "Header 5X2_SWD"))
    )
    (comp (ref "J12")
      (value "FPGA GPIO")
      (footprint "SWD_10_pin")
      (description "Header, 5-Pin, Dual row")
      (fields (field (name "MANUFACTURER") "Harwin Inc"))
      (libsource (lib "LimeMicroAltiumLib_schLib") (part "Header 5X2_SWD"))
    )
    (comp (ref "J13")
      (value "FAN")
      (footprint "HDR_1x2")
      (fields (field (name "ASSEMBLY INFO") "NF") (field (name "MANUFACTURER") "3M"))
      (libsource (lib "") (part "Jumper_1"))
    )
    (comp (ref "J14")
      (value "FAN")
      (footprint "HDR_1x2_HALF_PITCH")
      (fields (field (name "MANUFACTURER") "Sullins Connector Solutions"))
      (libsource (lib "LimeFPGAboard_schLib") (part "Jumper"))
    )
    (comp (ref "R51")
      (value "0R")
      (footprint "RES0402")
      (fields (field (name "MANUFACTURER") "Yageo"))
      (libsource (lib "LimeFPGAboard_schLib") (part "Res_0402"))
    )
    (comp (ref "R52")
      (value "0R")
      (footprint "RES0402")
      (fields (field (name "MANUFACTURER") "Yageo") (field (name "ASSEMBLY INFO") "NF"))
      (libsource (lib "LimeFPGAboard_schLib") (part "Res_0402"))
    )
    (comp (ref "R53")
      (value "0R")
      (footprint "RES0402")
      (fields (field (name "MANUFACTURER") "Yageo") (field (name "ASSEMBLY INFO") "NF"))
      (libsource (lib "LimeFPGAboard_schLib") (part "Res_0402"))
    )
    (comp (ref "R54")
      (value "0R")
      (footprint "RES0402")
      (fields (field (name "MANUFACTURER") "Yageo"))
      (libsource (lib "LimeFPGAboard_schLib") (part "Res_0402"))
    )
    (comp (ref "R55")
      (value "10k, 1%")
      (footprint "RES0402")
      (fields (field (name "MANUFACTURER") "Yageo") (field (name "TOLERANCE") "±1%"))
      (libsource (lib "LimeMicroAltiumLib_schLib") (part "Res_0402"))
    )
    (comp (ref "R56")
      (value "0R")
      (footprint "RES0402")
      (fields (field (name "MANUFACTURER") "Yageo"))
      (libsource (lib "LimeFPGAboard_schLib") (part "Res_0402"))
    )
    (comp (ref "R57")
      (value "0R")
      (footprint "RES0402")
      (fields (field (name "MANUFACTURER") "Yageo") (field (name "ASSEMBLY INFO") "NF"))
      (libsource (lib "LimeFPGAboard_schLib") (part "Res_0402"))
    )
    (comp (ref "R58")
      (value "10k, 1%")
      (footprint "RES0402")
      (fields (field (name "MANUFACTURER") "Yageo") (field (name "TOLERANCE") "±1%"))
      (libsource (lib "LimeMicroAltiumLib_schLib") (part "Res_0402"))
    )
    (comp (ref "R59")
      (value "0R")
      (footprint "RES0402")
      (fields (field (name "MANUFACTURER") "Yageo"))
      (libsource (lib "LimeFPGAboard_schLib") (part "Res_0402"))
    )
    (comp (ref "R60")
      (value "0R")
      (footprint "RES0402")
      (fields (field (name "MANUFACTURER") "Yageo") (field (name "ASSEMBLY INFO") "NF"))
      (libsource (lib "LimeFPGAboard_schLib") (part "Res_0402"))
    )
    (comp (ref "R61")
      (value "0R")
      (footprint "RES0402")
      (fields (field (name "MANUFACTURER") "Yageo"))
      (libsource (lib "LimeFPGAboard_schLib") (part "Res_0402"))
    )
    (comp (ref "R62")
      (value "1k, 1%")
      (footprint "RES0402")
      (fields (field (name "MANUFACTURER") "Stackpole Electronics Inc") (field (name "TOLERANCE") "±1%"))
      (libsource (lib "LimeMicroAltiumLib_schLib") (part "Res_0402"))
    )
    (comp (ref "R63")
      (value "0R")
      (footprint "RES0402")
      (fields (field (name "MANUFACTURER") "Yageo") (field (name "ASSEMBLY INFO") "NF"))
      (libsource (lib "LimeFPGAboard_schLib") (part "Res_0402"))
    )
    (comp (ref "R64")
      (value "0R")
      (footprint "RES0402")
      (fields (field (name "MANUFACTURER") "Yageo"))
      (libsource (lib "LimeFPGAboard_schLib") (part "Res_0402"))
    )
    (comp (ref "R65")
      (value "0R")
      (footprint "RES0402")
      (fields (field (name "MANUFACTURER") "Yageo") (field (name "ASSEMBLY INFO") "NF"))
      (libsource (lib "LimeFPGAboard_schLib") (part "Res_0402"))
    )
    (comp (ref "R66")
      (value "10k, 1%")
      (footprint "RES0402")
      (fields (field (name "MANUFACTURER") "Yageo") (field (name "TOLERANCE") "±1%"))
      (libsource (lib "LimeMicroAltiumLib_schLib") (part "Res_0402"))
    )
    (comp (ref "R67")
      (value "10k, 1%")
      (footprint "RES0402")
      (fields (field (name "MANUFACTURER") "Yageo") (field (name "TOLERANCE") "±1%"))
      (libsource (lib "LimeMicroAltiumLib_schLib") (part "Res_0402"))
    )
    (comp (ref "R68")
      (value "22R")
      (footprint "RES0402")
      (fields (field (name "TOLERANCE") "±1%") (field (name "MANUFACTURER") "Yageo"))
      (libsource (lib "LimeFPGAboard_schLib") (part "Res_0402"))
    )
    (comp (ref "R69")
      (value "100K")
      (footprint "RES0402")
      (fields
        (field (name "TOLERANCE") "±5%")
        (field (name "MANUFACTURER") "Panasonic Electronic Components")
      )
      (libsource (lib "LimeFPGAboard_schLib") (part "Res_0402"))
    )
    (comp (ref "R70")
      (value "4K7")
      (footprint "RES0402")
      (fields (field (name "TOLERANCE") "±5%") (field (name "MANUFACTURER") "Stackpole Electronics Inc."))
      (libsource (lib "LimeFPGAboard_schLib") (part "Res_0402"))
    )
    (comp (ref "R71")
      (value "4K7")
      (footprint "RES0402")
      (fields (field (name "TOLERANCE") "±5%") (field (name "MANUFACTURER") "Stackpole Electronics Inc."))
      (libsource (lib "LimeFPGAboard_schLib") (part "Res_0402"))
    )
    (comp (ref "R72")
      (value "0R")
      (footprint "RES0402")
      (fields (field (name "MANUFACTURER") "Yageo"))
      (libsource (lib "LimeFPGAboard_schLib") (part "Res_0402"))
    )
    (comp (ref "R73")
      (value "4K7")
      (footprint "RES0402")
      (fields (field (name "TOLERANCE") "±5%") (field (name "MANUFACTURER") "Stackpole Electronics Inc."))
      (libsource (lib "LimeFPGAboard_schLib") (part "Res_0402"))
    )
    (comp (ref "R74")
      (value "0R")
      (footprint "RES0402")
      (fields (field (name "MANUFACTURER") "Yageo") (field (name "ASSEMBLY INFO") "NF"))
      (libsource (lib "LimeFPGAboard_schLib") (part "Res_0402"))
    )
    (comp (ref "VT7")
      (value "NDS331N")
      (footprint "SOT23-3")
      (fields (field (name "MANUFACTURER") "Fairchild Semiconductor"))
      (libsource (lib "LimeFPGAboard_schLib") (part "NDS331N"))
    )
  )
  (nets
    (net (code "1") (name "/EXP_AS_SS") (class "Default")
      (node (ref "R74") (pin "1") (pinfunction "1_1") (pintype "passive"))
    )
    (net (code "2") (name "/EXP_AS_SW") (class "Default")
      (node (ref "R64") (pin "2") (pinfunction "2_2") (pintype "passive"))
    )
    (net (code "3") (name "/FAN_CTRL") (class "Default")
      (node (ref "R65") (pin "2") (pinfunction "2_2") (pintype "passive"))
      (node (ref "R67") (pin "1") (pinfunction "1_1") (pintype "passive"))
      (node (ref "VT7") (pin "G") (pinfunction "G_G") (pintype "passive"))
    )
    (net (code "4") (name "/FLASH_AS_MISO") (class "Default")
      (node (ref "IC10") (pin "2") (pinfunction "Q_2") (pintype "passive"))
      (node (ref "IC9") (pin "7") (pinfunction "COM2_7") (pintype "passive"))
    )
    (net (code "5") (name "/FLASH_AS_MOSI") (class "Default")
      (node (ref "IC10") (pin "5") (pinfunction "D_5") (pintype "passive"))
      (node (ref "IC9") (pin "4") (pinfunction "COM1_4") (pintype "passive"))
    )
    (net (code "6") (name "/FLASH_AS_SCLK") (class "Default")
      (node (ref "IC10") (pin "6") (pinfunction "C_6") (pintype "passive"))
      (node (ref "IC9") (pin "9") (pinfunction "COM3_9") (pintype "passive"))
      (node (ref "R69") (pin "1") (pinfunction "1_1") (pintype "passive"))
    )
    (net (code "7") (name "/FLASH_AS_SS") (class "Default")
      (node (ref "IC10") (pin "1") (pinfunction "S_1") (pintype "passive"))
      (node (ref "IC9") (pin "12") (pinfunction "COM4_12") (pintype "passive"))
      (node (ref "R70") (pin "2") (pinfunction "2_2") (pintype "passive"))
    )
    (net (code "8") (name "/FPGA_AS_ASDO") (class "Default")
      (node (ref "IC9") (pin "3") (pinfunction "NO1_3") (pintype "passive"))
    )
    (net (code "9") (name "/FPGA_AS_DATA0") (class "Default")
      (node (ref "R68") (pin "2") (pinfunction "2_2") (pintype "passive"))
    )
    (net (code "10") (name "/FPGA_AS_DCLK") (class "Default")
      (node (ref "IC8") (pin "K2") (pinfunction "DCLK_K2") (pintype "bidirectional"))
      (node (ref "IC9") (pin "10") (pinfunction "NO3_10") (pintype "passive"))
    )
    (net (code "11") (name "/FPGA_AS_NCSO") (class "Default")
      (node (ref "IC9") (pin "13") (pinfunction "NO4_13") (pintype "passive"))
    )
    (net (code "12") (name "/FPGA_CONF_DONE") (class "Default")
      (node (ref "IC8") (pin "M18") (pinfunction "CONF_DONE_M18") (pintype "bidirectional"))
    )
    (net (code "13") (name "/FPGA_GPIO0") (class "Default")
      (node (ref "J12") (pin "1") (pinfunction "1_1") (pintype "passive"))
    )
    (net (code "14") (name "/FPGA_GPIO1") (class "Default")
      (node (ref "J12") (pin "2") (pinfunction "2_2") (pintype "passive"))
    )
    (net (code "15") (name "/FPGA_GPIO2") (class "Default")
      (node (ref "J12") (pin "3") (pinfunction "3_3") (pintype "passive"))
    )
    (net (code "16") (name "/FPGA_GPIO3") (class "Default")
      (node (ref "J12") (pin "4") (pinfunction "4_4") (pintype "passive"))
    )
    (net (code "17") (name "/FPGA_GPIO4") (class "Default")
      (node (ref "J12") (pin "5") (pinfunction "5_5") (pintype "passive"))
    )
    (net (code "18") (name "/FPGA_GPIO5") (class "Default")
      (node (ref "J12") (pin "6") (pinfunction "6_6") (pintype "passive"))
    )
    (net (code "19") (name "/FPGA_GPIO6") (class "Default")
      (node (ref "J12") (pin "7") (pinfunction "7_7") (pintype "passive"))
    )
    (net (code "20") (name "/FPGA_GPIO7") (class "Default")
      (node (ref "J12") (pin "8") (pinfunction "8_8") (pintype "passive"))
    )
    (net (code "21") (name "/FPGA_JTAG_TCK") (class "Default")
      (node (ref "IC8") (pin "L2") (pinfunction "TCK_L2") (pintype "input"))
      (node (ref "J11") (pin "1") (pinfunction "1_1") (pintype "passive"))
      (node (ref "R62") (pin "1") (pinfunction "1_1") (pintype "passive"))
    )
    (net (code "22") (name "/FPGA_JTAG_TDI") (class "Default")
      (node (ref "IC8") (pin "L5") (pinfunction "TDI_L5") (pintype "input"))
      (node (ref "J11") (pin "9") (pinfunction "9_9") (pintype "passive"))
      (node (ref "R58") (pin "1") (pinfunction "1_1") (pintype "passive"))
    )
    (net (code "23") (name "/FPGA_JTAG_TDO") (class "Default")
      (node (ref "IC8") (pin "L4") (pinfunction "TDO_L4") (pintype "output"))
      (node (ref "J11") (pin "3") (pinfunction "3_3") (pintype "passive"))
    )
    (net (code "24") (name "/FPGA_JTAG_TMS") (class "Default")
      (node (ref "IC8") (pin "L1") (pinfunction "TMS_L1") (pintype "input"))
      (node (ref "J11") (pin "5") (pinfunction "5_5") (pintype "passive"))
      (node (ref "R55") (pin "1") (pinfunction "1_1") (pintype "passive"))
    )
    (net (code "25") (name "/FPGA_NCONFIG") (class "Default")
      (node (ref "IC8") (pin "K5") (pinfunction "nCONFIG_K5") (pintype "input"))
    )
    (net (code "26") (name "/FPGA_NSTATUS") (class "Default")
      (node (ref "IC8") (pin "K6") (pinfunction "nSTATUS_K6") (pintype "bidirectional"))
    )
    (net (code "27") (name "/FX3_PCLK") (class "Default")
      (node (ref "IC8") (pin "T21") (pinfunction "CLK6,_DIFFCLK_3p_T21") (pintype "input"))
    )
    (net (code "28") (name "/FX3_SPI_AS_SS") (class "Default")
      (node (ref "R72") (pin "1") (pinfunction "1_1") (pintype "passive"))
    )
    (net (code "29") (name "/FX3_SPI_MISO") (class "Default")
      (node (ref "IC9") (pin "5") (pinfunction "NC2_5") (pintype "passive"))
    )
    (net (code "30") (name "/FX3_SPI_MOSI") (class "Default")
      (node (ref "IC9") (pin "2") (pinfunction "NC1_2") (pintype "passive"))
    )
    (net (code "31") (name "/FX3_SPI_SCLK") (class "Default")
      (node (ref "IC9") (pin "11") (pinfunction "NC3_11") (pintype "passive"))
    )
    (net (code "32") (name "/LM75_OS") (class "Default")
      (node (ref "R65") (pin "1") (pinfunction "1_1") (pintype "passive"))
    )
    (net (code "33") (name "/LMK_CLK") (class "Default")
      (node (ref "IC8") (pin "B12") (pinfunction "CLK9,_DIFFCLK_5p_B12") (pintype "input"))
    )
    (net (code "34") (name "/LMS_MCLK1") (class "Default")
      (node (ref "IC8") (pin "G21") (pinfunction "CLK4,_DIFFCLK_2p_G21") (pintype "input"))
    )
    (net (code "35") (name "/LMS_MCLK2") (class "Default")
      (node (ref "IC8") (pin "B11") (pinfunction "CLK11,_DIFFCLK_4p_B11") (pintype "input"))
    )
    (net (code "36") (name "/MSEL0") (class "Default")
      (node (ref "IC8") (pin "M17") (pinfunction "MSEL0_M17") (pintype "input"))
      (node (ref "R51") (pin "1") (pinfunction "1_1") (pintype "passive"))
      (node (ref "R52") (pin "2") (pinfunction "2_2") (pintype "passive"))
    )
    (net (code "37") (name "/MSEL1") (class "Default")
      (node (ref "IC8") (pin "L18") (pinfunction "MSEL1_L18") (pintype "input"))
      (node (ref "R53") (pin "1") (pinfunction "1_1") (pintype "passive"))
      (node (ref "R54") (pin "2") (pinfunction "2_2") (pintype "passive"))
    )
    (net (code "38") (name "/MSEL2") (class "Default")
      (node (ref "IC8") (pin "L17") (pinfunction "MSEL2_L17") (pintype "input"))
      (node (ref "R56") (pin "1") (pinfunction "1_1") (pintype "passive"))
      (node (ref "R57") (pin "2") (pinfunction "2_2") (pintype "passive"))
    )
    (net (code "39") (name "/MSEL3") (class "Default")
      (node (ref "IC8") (pin "K20") (pinfunction "MSEL3_K20") (pintype "input"))
      (node (ref "R59") (pin "1") (pinfunction "1_1") (pintype "passive"))
      (node (ref "R60") (pin "2") (pinfunction "2_2") (pintype "passive"))
    )
    (net (code "40") (name "/SI_CLK0") (class "Default")
      (node (ref "IC8") (pin "T2") (pinfunction "CLK2,_DIFFCLK_1p_T2") (pintype "input"))
    )
    (net (code "41") (name "/SI_CLK1") (class "Default")
      (node (ref "IC8") (pin "AA12") (pinfunction "CLK13,_DIFFCLK_7p_AA12") (pintype "input"))
    )
    (net (code "42") (name "/SI_CLK2") (class "Default")
      (node (ref "IC8") (pin "AB12") (pinfunction "CLK12,_DIFFCLK_7n_AB12") (pintype "input"))
    )
    (net (code "43") (name "/SI_CLK3") (class "Default")
      (node (ref "IC8") (pin "T22") (pinfunction "CLK7,_DIFFCLK_3n_T22") (pintype "input"))
    )
    (net (code "44") (name "/SI_CLK5") (class "Default")
      (node (ref "IC8") (pin "G1") (pinfunction "CLK1,_DIFFCLK_0n_G1") (pintype "input"))
    )
    (net (code "45") (name "/SI_CLK6") (class "Default")
      (node (ref "IC8") (pin "AA11") (pinfunction "CLK15,_DIFFCLK_6p_AA11") (pintype "input"))
    )
    (net (code "46") (name "/SI_CLK7") (class "Default")
      (node (ref "IC8") (pin "AB11") (pinfunction "CLK14,_DIFFCLK_6n_AB11") (pintype "input"))
    )
    (net (code "47") (name "GND") (class "Default")
      (node (ref "C115") (pin "1") (pinfunction "1_1") (pintype "passive"))
      (node (ref "C116") (pin "1") (pinfunction "1_1") (pintype "passive"))
      (node (ref "C117") (pin "1") (pinfunction "1_1") (pintype "passive"))
      (node (ref "C118") (pin "2") (pinfunction "2_2") (pintype "passive"))
      (node (ref "C119") (pin "2") (pinfunction "2_2") (pintype "passive"))
      (node (ref "C120") (pin "1") (pinfunction "1_1") (pintype "passive"))
      (node (ref "C121") (pin "1") (pinfunction "1_1") (pintype "passive"))
      (node (ref "C122") (pin "1") (pinfunction "1_1") (pintype "passive"))
      (node (ref "C123") (pin "2") (pinfunction "2_2") (pintype "passive"))
      (node (ref "C124") (pin "2") (pinfunction "2_2") (pintype "passive"))
      (node (ref "C125") (pin "2") (pinfunction "2_2") (pintype "passive"))
      (node (ref "C126") (pin "1") (pinfunction "1_1") (pintype "passive"))
      (node (ref "C127") (pin "1") (pinfunction "1_1") (pintype "passive"))
      (node (ref "C128") (pin "1") (pinfunction "1_1") (pintype "passive"))
      (node (ref "C129") (pin "1") (pinfunction "1_1") (pintype "passive"))
      (node (ref "C130") (pin "1") (pinfunction "1_1") (pintype "passive"))
      (node (ref "C131") (pin "2") (pinfunction "2_2") (pintype "passive"))
      (node (ref "C132") (pin "1") (pinfunction "1_1") (pintype "passive"))
      (node (ref "C133") (pin "1") (pinfunction "1_1") (pintype "passive"))
      (node (ref "C134") (pin "1") (pinfunction "1_1") (pintype "passive"))
      (node (ref "C135") (pin "1") (pinfunction "1_1") (pintype "passive"))
      (node (ref "C136") (pin "2") (pinfunction "2_2") (pintype "passive"))
      (node (ref "C137") (pin "1") (pinfunction "1_1") (pintype "passive"))
      (node (ref "C138") (pin "1") (pinfunction "1_1") (pintype "passive"))
      (node (ref "C139") (pin "1") (pinfunction "1_1") (pintype "passive"))
      (node (ref "C140") (pin "1") (pinfunction "1_1") (pintype "passive"))
      (node (ref "C141") (pin "2") (pinfunction "2_2") (pintype "passive"))
      (node (ref "C142") (pin "1") (pinfunction "1_1") (pintype "passive"))
      (node (ref "C143") (pin "1") (pinfunction "1_1") (pintype "passive"))
      (node (ref "C144") (pin "1") (pinfunction "1_1") (pintype "passive"))
      (node (ref "C145") (pin "1") (pinfunction "1_1") (pintype "passive"))
      (node (ref "C146") (pin "2") (pinfunction "2_2") (pintype "passive"))
      (node (ref "C147") (pin "2") (pinfunction "2_2") (pintype "passive"))
      (node (ref "C148") (pin "2") (pinfunction "2_2") (pintype "passive"))
      (node (ref "C149") (pin "2") (pinfunction "2_2") (pintype "passive"))
      (node (ref "C150") (pin "2") (pinfunction "2_2") (pintype "passive"))
      (node (ref "C151") (pin "2") (pinfunction "2_2") (pintype "passive"))
      (node (ref "C152") (pin "2") (pinfunction "2_2") (pintype "passive"))
      (node (ref "C153") (pin "2") (pinfunction "2_2") (pintype "passive"))
      (node (ref "C154") (pin "2") (pinfunction "2_2") (pintype "passive"))
      (node (ref "C155") (pin "2") (pinfunction "2_2") (pintype "passive"))
      (node (ref "C156") (pin "2") (pinfunction "2_2") (pintype "passive"))
      (node (ref "C157") (pin "2") (pinfunction "2_2") (pintype "passive"))
      (node (ref "C158") (pin "2") (pinfunction "2_2") (pintype "passive"))
      (node (ref "C159") (pin "2") (pinfunction "2_2") (pintype "passive"))
      (node (ref "C160") (pin "2") (pinfunction "2_2") (pintype "passive"))
      (node (ref "C161") (pin "2") (pinfunction "2_2") (pintype "passive"))
      (node (ref "C162") (pin "2") (pinfunction "2_2") (pintype "passive"))
      (node (ref "C163") (pin "2") (pinfunction "2_2") (pintype "passive"))
      (node (ref "C164") (pin "2") (pinfunction "2_2") (pintype "passive"))
      (node (ref "C165") (pin "2") (pinfunction "2_2") (pintype "passive"))
      (node (ref "C166") (pin "2") (pinfunction "2_2") (pintype "passive"))
      (node (ref "C167") (pin "2") (pinfunction "2_2") (pintype "passive"))
      (node (ref "C168") (pin "2") (pinfunction "2_2") (pintype "passive"))
      (node (ref "C169") (pin "2") (pinfunction "2_2") (pintype "passive"))
      (node (ref "C170") (pin "2") (pinfunction "2_2") (pintype "passive"))
      (node (ref "C171") (pin "2") (pinfunction "2_2") (pintype "passive"))
      (node (ref "C172") (pin "2") (pinfunction "2_2") (pintype "passive"))
      (node (ref "C173") (pin "2") (pinfunction "2_2") (pintype "passive"))
      (node (ref "C174") (pin "2") (pinfunction "2_2") (pintype "passive"))
      (node (ref "C175") (pin "2") (pinfunction "2_2") (pintype "passive"))
      (node (ref "C176") (pin "2") (pinfunction "2_2") (pintype "passive"))
      (node (ref "C177") (pin "2") (pinfunction "2_2") (pintype "passive"))
      (node (ref "C178") (pin "2") (pinfunction "2_2") (pintype "passive"))
      (node (ref "C179") (pin "2") (pinfunction "2_2") (pintype "passive"))
      (node (ref "C180") (pin "2") (pinfunction "2_2") (pintype "passive"))
      (node (ref "C181") (pin "2") (pinfunction "2_2") (pintype "passive"))
      (node (ref "C182") (pin "2") (pinfunction "2_2") (pintype "passive"))
      (node (ref "C183") (pin "2") (pinfunction "2_2") (pintype "passive"))
      (node (ref "C184") (pin "2") (pinfunction "2_2") (pintype "passive"))
      (node (ref "C185") (pin "2") (pinfunction "2_2") (pintype "passive"))
      (node (ref "C186") (pin "2") (pinfunction "2_2") (pintype "passive"))
      (node (ref "C187") (pin "2") (pinfunction "2_2") (pintype "passive"))
      (node (ref "C188") (pin "2") (pinfunction "2_2") (pintype "passive"))
      (node (ref "C189") (pin "2") (pinfunction "2_2") (pintype "passive"))
      (node (ref "C190") (pin "2") (pinfunction "2_2") (pintype "passive"))
      (node (ref "C191") (pin "2") (pinfunction "2_2") (pintype "passive"))
      (node (ref "C192") (pin "2") (pinfunction "2_2") (pintype "passive"))
      (node (ref "C193") (pin "2") (pinfunction "2_2") (pintype "passive"))
      (node (ref "C194") (pin "2") (pinfunction "2_2") (pintype "passive"))
      (node (ref "C195") (pin "2") (pinfunction "2_2") (pintype "passive"))
      (node (ref "C196") (pin "2") (pinfunction "2_2") (pintype "passive"))
      (node (ref "C197") (pin "2") (pinfunction "2_2") (pintype "passive"))
      (node (ref "C198") (pin "2") (pinfunction "2_2") (pintype "passive"))
      (node (ref "C199") (pin "2") (pinfunction "2_2") (pintype "passive"))
      (node (ref "C200") (pin "2") (pinfunction "2_2") (pintype "passive"))
      (node (ref "C201") (pin "2") (pinfunction "2_2") (pintype "passive"))
      (node (ref "C202") (pin "2") (pinfunction "2_2") (pintype "passive"))
      (node (ref "C203") (pin "2") (pinfunction "2_2") (pintype "passive"))
      (node (ref "C204") (pin "2") (pinfunction "2_2") (pintype "passive"))
      (node (ref "C205") (pin "2") (pinfunction "2_2") (pintype "passive"))
      (node (ref "C206") (pin "2") (pinfunction "2_2") (pintype "passive"))
      (node (ref "C207") (pin "2") (pinfunction "2_2") (pintype "passive"))
      (node (ref "C208") (pin "2") (pinfunction "2_2") (pintype "passive"))
      (node (ref "C209") (pin "2") (pinfunction "2_2") (pintype "passive"))
      (node (ref "C210") (pin "2") (pinfunction "2_2") (pintype "passive"))
      (node (ref "C211") (pin "2") (pinfunction "2_2") (pintype "passive"))
      (node (ref "C212") (pin "2") (pinfunction "2_2") (pintype "passive"))
      (node (ref "C213") (pin "2") (pinfunction "2_2") (pintype "passive"))
      (node (ref "C214") (pin "2") (pinfunction "2_2") (pintype "passive"))
      (node (ref "C215") (pin "2") (pinfunction "2_2") (pintype "passive"))
      (node (ref "C216") (pin "2") (pinfunction "2_2") (pintype "passive"))
      (node (ref "C217") (pin "2") (pinfunction "2_2") (pintype "passive"))
      (node (ref "C218") (pin "2") (pinfunction "2_2") (pintype "passive"))
      (node (ref "C219") (pin "2") (pinfunction "2_2") (pintype "passive"))
      (node (ref "C220") (pin "2") (pinfunction "2_2") (pintype "passive"))
      (node (ref "IC10") (pin "4") (pinfunction "GND_4") (pintype "passive"))
      (node (ref "IC8") (pin "A1") (pinfunction "GND_A1") (pintype "power_in"))
      (node (ref "IC8") (pin "A11") (pinfunction "CLK10,_DIFFCLK_4n_A11") (pintype "input"))
      (node (ref "IC8") (pin "A12") (pinfunction "CLK8,_DIFFCLK_5n_A12") (pintype "input"))
      (node (ref "IC8") (pin "A22") (pinfunction "GND_A22") (pintype "power_in"))
      (node (ref "IC8") (pin "AA2") (pinfunction "GND_AA2") (pintype "power_in"))
      (node (ref "IC8") (pin "AA22") (pinfunction "GND_AA22") (pintype "power_in"))
      (node (ref "IC8") (pin "AB1") (pinfunction "GND_AB1") (pintype "power_in"))
      (node (ref "IC8") (pin "AB22") (pinfunction "GND_AB22") (pintype "power_in"))
      (node (ref "IC8") (pin "AB6") (pinfunction "GND_AB6") (pintype "power_in"))
      (node (ref "IC8") (pin "C11") (pinfunction "GND_C11") (pintype "power_in"))
      (node (ref "IC8") (pin "C12") (pinfunction "GND_C12") (pintype "power_in"))
      (node (ref "IC8") (pin "C14") (pinfunction "GND_C14") (pintype "power_in"))
      (node (ref "IC8") (pin "C16") (pinfunction "GND_C16") (pintype "power_in"))
      (node (ref "IC8") (pin "C18") (pinfunction "GND_C18") (pintype "power_in"))
      (node (ref "IC8") (pin "C5") (pinfunction "GND_C5") (pintype "power_in"))
      (node (ref "IC8") (pin "C9") (pinfunction "GND_C9") (pintype "power_in"))
      (node (ref "IC8") (pin "D3") (pinfunction "GND_D3") (pintype "power_in"))
      (node (ref "IC8") (pin "D8") (pinfunction "GND_D8") (pintype "power_in"))
      (node (ref "IC8") (pin "E18") (pinfunction "GNDA2_E18") (pintype "power_in"))
      (node (ref "IC8") (pin "E20") (pinfunction "GND_E20") (pintype "power_in"))
      (node (ref "IC8") (pin "F12") (pinfunction "GND_F12") (pintype "power_in"))
      (node (ref "IC8") (pin "F3") (pinfunction "GND_F3") (pintype "power_in"))
      (node (ref "IC8") (pin "F5") (pinfunction "GNDA3_F5") (pintype "power_in"))
      (node (ref "IC8") (pin "G2") (pinfunction "GND_G2") (pintype "power_in"))
      (node (ref "IC8") (pin "G20") (pinfunction "GND_G20") (pintype "power_in"))
      (node (ref "IC8") (pin "G22") (pinfunction "CLK5,_DIFFCLK_2n_G22") (pintype "input"))
      (node (ref "IC8") (pin "H12") (pinfunction "GND_H12") (pintype "power_in"))
      (node (ref "IC8") (pin "H13") (pinfunction "GND_H13") (pintype "power_in"))
      (node (ref "IC8") (pin "H3") (pinfunction "GND_H3") (pintype "power_in"))
      (node (ref "IC8") (pin "J15") (pinfunction "GND_J15") (pintype "power_in"))
      (node (ref "IC8") (pin "J19") (pinfunction "GND_J19") (pintype "power_in"))
      (node (ref "IC8") (pin "J9") (pinfunction "GND_J9") (pintype "power_in"))
      (node (ref "IC8") (pin "K10") (pinfunction "GND_K10") (pintype "power_in"))
      (node (ref "IC8") (pin "K11") (pinfunction "GND_K11") (pintype "power_in"))
      (node (ref "IC8") (pin "K12") (pinfunction "GND_K12") (pintype "power_in"))
      (node (ref "IC8") (pin "K13") (pinfunction "GND_K13") (pintype "power_in"))
      (node (ref "IC8") (pin "K16") (pinfunction "GND_K16") (pintype "power_in"))
      (node (ref "IC8") (pin "K3") (pinfunction "GND_K3") (pintype "power_in"))
      (node (ref "IC8") (pin "L10") (pinfunction "GND_L10") (pintype "power_in"))
      (node (ref "IC8") (pin "L11") (pinfunction "GND_L11") (pintype "power_in"))
      (node (ref "IC8") (pin "L12") (pinfunction "GND_L12") (pintype "power_in"))
      (node (ref "IC8") (pin "L13") (pinfunction "GND_L13") (pintype "power_in"))
      (node (ref "IC8") (pin "L15") (pinfunction "GND_L15") (pintype "power_in"))
      (node (ref "IC8") (pin "L20") (pinfunction "GND_L20") (pintype "power_in"))
      (node (ref "IC8") (pin "L3") (pinfunction "nCE_L3") (pintype "input"))
      (node (ref "IC8") (pin "M10") (pinfunction "GND_M10") (pintype "power_in"))
      (node (ref "IC8") (pin "M11") (pinfunction "GND_M11") (pintype "power_in"))
      (node (ref "IC8") (pin "M12") (pinfunction "GND_M12") (pintype "power_in"))
      (node (ref "IC8") (pin "M13") (pinfunction "GND_M13") (pintype "power_in"))
      (node (ref "IC8") (pin "N10") (pinfunction "GND_N10") (pintype "power_in"))
      (node (ref "IC8") (pin "N11") (pinfunction "GND_N11") (pintype "power_in"))
      (node (ref "IC8") (pin "N12") (pinfunction "GND_N12") (pintype "power_in"))
      (node (ref "IC8") (pin "N13") (pinfunction "GND_N13") (pintype "power_in"))
      (node (ref "IC8") (pin "N15") (pinfunction "GND_N15") (pintype "power_in"))
      (node (ref "IC8") (pin "N3") (pinfunction "GND_N3") (pintype "power_in"))
      (node (ref "IC8") (pin "P19") (pinfunction "GND_P19") (pintype "power_in"))
      (node (ref "IC8") (pin "P8") (pinfunction "GND_P8") (pintype "power_in"))
      (node (ref "IC8") (pin "R11") (pinfunction "GND_R11") (pintype "power_in"))
      (node (ref "IC8") (pin "R13") (pinfunction "GND_R13") (pintype "power_in"))
      (node (ref "IC8") (pin "R3") (pinfunction "GND_R3") (pintype "power_in"))
      (node (ref "IC8") (pin "R9") (pinfunction "GND_R9") (pintype "power_in"))
      (node (ref "IC8") (pin "T1") (pinfunction "CLK3,_DIFFCLK_1n_T1") (pintype "input"))
      (node (ref "IC8") (pin "T20") (pinfunction "GND_T20") (pintype "power_in"))
      (node (ref "IC8") (pin "U3") (pinfunction "GND_U3") (pintype "power_in"))
      (node (ref "IC8") (pin "U5") (pinfunction "GNDA1_U5") (pintype "power_in"))
      (node (ref "IC8") (pin "V18") (pinfunction "GNDA4_V18") (pintype "power_in"))
      (node (ref "IC8") (pin "V20") (pinfunction "GND_V20") (pintype "power_in"))
      (node (ref "IC8") (pin "W3") (pinfunction "GND_W3") (pintype "power_in"))
      (node (ref "IC8") (pin "Y11") (pinfunction "GND_Y11") (pintype "power_in"))
      (node (ref "IC8") (pin "Y12") (pinfunction "GND_Y12") (pintype "power_in"))
      (node (ref "IC8") (pin "Y15") (pinfunction "GND_Y15") (pintype "power_in"))
      (node (ref "IC8") (pin "Y16") (pinfunction "GND_Y16") (pintype "power_in"))
      (node (ref "IC8") (pin "Y18") (pinfunction "GND_Y18") (pintype "power_in"))
      (node (ref "IC8") (pin "Y20") (pinfunction "GND_Y20") (pintype "power_in"))
      (node (ref "IC8") (pin "Y5") (pinfunction "GND_Y5") (pintype "power_in"))
      (node (ref "IC8") (pin "Y9") (pinfunction "GND_Y9") (pintype "power_in"))
      (node (ref "IC9") (pin "15") (pinfunction "~{EN}_15") (pintype "passive"))
      (node (ref "IC9") (pin "8") (pinfunction "GND_8") (pintype "passive"))
      (node (ref "J11") (pin "10") (pinfunction "10_10") (pintype "passive"))
      (node (ref "J11") (pin "2") (pinfunction "2_2") (pintype "passive"))
      (node (ref "J12") (pin "9") (pinfunction "9_9") (pintype "passive"))
      (node (ref "R51") (pin "2") (pinfunction "2_2") (pintype "passive"))
      (node (ref "R53") (pin "2") (pinfunction "2_2") (pintype "passive"))
      (node (ref "R56") (pin "2") (pinfunction "2_2") (pintype "passive"))
      (node (ref "R59") (pin "2") (pinfunction "2_2") (pintype "passive"))
      (node (ref "R62") (pin "2") (pinfunction "2_2") (pintype "passive"))
      (node (ref "R67") (pin "2") (pinfunction "2_2") (pintype "passive"))
      (node (ref "R69") (pin "2") (pinfunction "2_2") (pintype "passive"))
      (node (ref "VT7") (pin "S") (pinfunction "S_S") (pintype "passive"))
    )
    (net (code "48") (name "Net-(IC9-IN)") (class "Default")
      (node (ref "IC9") (pin "1") (pinfunction "IN_1") (pintype "passive"))
      (node (ref "R64") (pin "1") (pinfunction "1_1") (pintype "passive"))
      (node (ref "R66") (pin "2") (pinfunction "2_2") (pintype "passive"))
    )
    (net (code "49") (name "Net-(IC9-NC4)") (class "Default")
      (node (ref "IC9") (pin "14") (pinfunction "NC4_14") (pintype "passive"))
      (node (ref "R72") (pin "2") (pinfunction "2_2") (pintype "passive"))
      (node (ref "R74") (pin "2") (pinfunction "2_2") (pintype "passive"))
    )
    (net (code "50") (name "Net-(IC9-NO2)") (class "Default")
      (node (ref "IC9") (pin "6") (pinfunction "NO2_6") (pintype "passive"))
      (node (ref "R68") (pin "1") (pinfunction "1_1") (pintype "passive"))
    )
    (net (code "51") (name "Net-(IC10-HOLD)") (class "Default")
      (node (ref "IC10") (pin "7") (pinfunction "HOLD_7") (pintype "passive"))
      (node (ref "R71") (pin "2") (pinfunction "2_2") (pintype "passive"))
    )
    (net (code "52") (name "Net-(IC10-W)") (class "Default")
      (node (ref "IC10") (pin "3") (pinfunction "W_3") (pintype "passive"))
      (node (ref "R73") (pin "2") (pinfunction "2_2") (pintype "passive"))
    )
    (net (code "53") (name "Net-(J12-Pad10)") (class "Default")
      (node (ref "J12") (pin "10") (pinfunction "10_10") (pintype "passive"))
      (node (ref "R61") (pin "2") (pinfunction "2_2") (pintype "passive"))
      (node (ref "R63") (pin "2") (pinfunction "2_2") (pintype "passive"))
    )
    (net (code "54") (name "Net-(J13-Pad1)") (class "Default")
      (node (ref "J13") (pin "1") (pinfunction "1_1") (pintype "passive"))
      (node (ref "J14") (pin "1") (pinfunction "1_1") (pintype "passive"))
      (node (ref "VT7") (pin "D") (pinfunction "D_D") (pintype "passive"))
    )
    (net (code "55") (name "VCC1P2") (class "Default")
      (node (ref "C115") (pin "2") (pinfunction "2_2") (pintype "passive"))
      (node (ref "C116") (pin "2") (pinfunction "2_2") (pintype "passive"))
      (node (ref "C117") (pin "2") (pinfunction "2_2") (pintype "passive"))
      (node (ref "C118") (pin "1") (pinfunction "1_1") (pintype "passive"))
      (node (ref "C119") (pin "1") (pinfunction "1_1") (pintype "passive"))
      (node (ref "C189") (pin "1") (pinfunction "1_1") (pintype "passive"))
      (node (ref "C190") (pin "1") (pinfunction "1_1") (pintype "passive"))
      (node (ref "C191") (pin "1") (pinfunction "1_1") (pintype "passive"))
      (node (ref "C192") (pin "1") (pinfunction "1_1") (pintype "passive"))
      (node (ref "C193") (pin "1") (pinfunction "1_1") (pintype "passive"))
      (node (ref "C194") (pin "1") (pinfunction "1_1") (pintype "passive"))
      (node (ref "C195") (pin "1") (pinfunction "1_1") (pintype "passive"))
      (node (ref "C196") (pin "1") (pinfunction "1_1") (pintype "passive"))
      (node (ref "C197") (pin "1") (pinfunction "1_1") (pintype "passive"))
      (node (ref "C198") (pin "1") (pinfunction "1_1") (pintype "passive"))
      (node (ref "C199") (pin "1") (pinfunction "1_1") (pintype "passive"))
      (node (ref "C200") (pin "1") (pinfunction "1_1") (pintype "passive"))
      (node (ref "C201") (pin "1") (pinfunction "1_1") (pintype "passive"))
      (node (ref "C202") (pin "1") (pinfunction "1_1") (pintype "passive"))
      (node (ref "C207") (pin "1") (pinfunction "1_1") (pintype "passive"))
      (node (ref "C208") (pin "1") (pinfunction "1_1") (pintype "passive"))
      (node (ref "C209") (pin "1") (pinfunction "1_1") (pintype "passive"))
      (node (ref "C210") (pin "1") (pinfunction "1_1") (pintype "passive"))
      (node (ref "C211") (pin "1") (pinfunction "1_1") (pintype "passive"))
      (node (ref "C212") (pin "1") (pinfunction "1_1") (pintype "passive"))
      (node (ref "C213") (pin "1") (pinfunction "1_1") (pintype "passive"))
      (node (ref "C214") (pin "1") (pinfunction "1_1") (pintype "passive"))
      (node (ref "C215") (pin "1") (pinfunction "1_1") (pintype "passive"))
      (node (ref "C216") (pin "1") (pinfunction "1_1") (pintype "passive"))
      (node (ref "C217") (pin "1") (pinfunction "1_1") (pintype "passive"))
      (node (ref "C218") (pin "1") (pinfunction "1_1") (pintype "passive"))
      (node (ref "C219") (pin "1") (pinfunction "1_1") (pintype "passive"))
      (node (ref "C220") (pin "1") (pinfunction "1_1") (pintype "passive"))
      (node (ref "FR36") (pin "1") (pinfunction "1_1") (pintype "passive"))
      (node (ref "IC8") (pin "G12") (pinfunction "VCCINT_G12") (pintype "power_in"))
      (node (ref "IC8") (pin "H9") (pinfunction "VCCINT_H9") (pintype "power_in"))
      (node (ref "IC8") (pin "J10") (pinfunction "VCCINT_J10") (pintype "power_in"))
      (node (ref "IC8") (pin "J11") (pinfunction "VCCINT_J11") (pintype "power_in"))
      (node (ref "IC8") (pin "J12") (pinfunction "VCCINT_J12") (pintype "power_in"))
      (node (ref "IC8") (pin "J13") (pinfunction "VCCINT_J13") (pintype "power_in"))
      (node (ref "IC8") (pin "J14") (pinfunction "VCCINT_J14") (pintype "power_in"))
      (node (ref "IC8") (pin "J16") (pinfunction "VCCINT_J16") (pintype "power_in"))
      (node (ref "IC8") (pin "K14") (pinfunction "VCCINT_K14") (pintype "power_in"))
      (node (ref "IC8") (pin "K15") (pinfunction "VCCINT_K15") (pintype "power_in"))
      (node (ref "IC8") (pin "K9") (pinfunction "VCCINT_K9") (pintype "power_in"))
      (node (ref "IC8") (pin "L14") (pinfunction "VCCINT_L14") (pintype "power_in"))
      (node (ref "IC8") (pin "L16") (pinfunction "VCCINT_L16") (pintype "power_in"))
      (node (ref "IC8") (pin "L9") (pinfunction "VCCINT_L9") (pintype "power_in"))
      (node (ref "IC8") (pin "M14") (pinfunction "VCCINT_M14") (pintype "power_in"))
      (node (ref "IC8") (pin "M15") (pinfunction "VCCINT_M15") (pintype "power_in"))
      (node (ref "IC8") (pin "M9") (pinfunction "VCCINT_M9") (pintype "power_in"))
      (node (ref "IC8") (pin "N14") (pinfunction "VCCINT_N14") (pintype "power_in"))
      (node (ref "IC8") (pin "N9") (pinfunction "VCCINT_N9") (pintype "power_in"))
      (node (ref "IC8") (pin "P10") (pinfunction "VCCINT_P10") (pintype "power_in"))
      (node (ref "IC8") (pin "P11") (pinfunction "VCCINT_P11") (pintype "power_in"))
      (node (ref "IC8") (pin "P12") (pinfunction "VCCINT_P12") (pintype "power_in"))
      (node (ref "IC8") (pin "P13") (pinfunction "VCCINT_P13") (pintype "power_in"))
      (node (ref "IC8") (pin "P14") (pinfunction "VCCINT_P14") (pintype "power_in"))
      (node (ref "IC8") (pin "P9") (pinfunction "VCCINT_P9") (pintype "power_in"))
      (node (ref "IC8") (pin "R10") (pinfunction "VCCINT_R10") (pintype "power_in"))
      (node (ref "IC8") (pin "R12") (pinfunction "VCCINT_R12") (pintype "power_in"))
      (node (ref "IC8") (pin "R8") (pinfunction "VCCINT_R8") (pintype "power_in"))
    )
    (net (code "56") (name "VCC1P2D_FPGA") (class "Default")
      (node (ref "C120") (pin "2") (pinfunction "2_2") (pintype "passive"))
      (node (ref "C121") (pin "2") (pinfunction "2_2") (pintype "passive"))
      (node (ref "C122") (pin "2") (pinfunction "2_2") (pintype "passive"))
      (node (ref "C123") (pin "1") (pinfunction "1_1") (pintype "passive"))
      (node (ref "C124") (pin "1") (pinfunction "1_1") (pintype "passive"))
      (node (ref "C203") (pin "1") (pinfunction "1_1") (pintype "passive"))
      (node (ref "C204") (pin "1") (pinfunction "1_1") (pintype "passive"))
      (node (ref "C205") (pin "1") (pinfunction "1_1") (pintype "passive"))
      (node (ref "C206") (pin "1") (pinfunction "1_1") (pintype "passive"))
      (node (ref "FR36") (pin "2") (pinfunction "2_2") (pintype "passive"))
      (node (ref "IC8") (pin "E17") (pinfunction "VCCD_PLL2_E17") (pintype "power_in"))
      (node (ref "IC8") (pin "F6") (pinfunction "VCCD_PLL3_F6") (pintype "power_in"))
      (node (ref "IC8") (pin "U6") (pinfunction "VCCD_PLL1_U6") (pintype "power_in"))
      (node (ref "IC8") (pin "V17") (pinfunction "VCCD_PLL4_V17") (pintype "power_in"))
    )
    (net (code "57") (name "VCC1P8") (class "Default")
      (node (ref "C126") (pin "2") (pinfunction "2_2") (pintype "passive"))
      (node (ref "C127") (pin "2") (pinfunction "2_2") (pintype "passive"))
      (node (ref "C128") (pin "2") (pinfunction "2_2") (pintype "passive"))
      (node (ref "C129") (pin "2") (pinfunction "2_2") (pintype "passive"))
      (node (ref "C130") (pin "2") (pinfunction "2_2") (pintype "passive"))
      (node (ref "C131") (pin "1") (pinfunction "1_1") (pintype "passive"))
      (node (ref "C171") (pin "1") (pinfunction "1_1") (pintype "passive"))
      (node (ref "C172") (pin "1") (pinfunction "1_1") (pintype "passive"))
      (node (ref "C173") (pin "1") (pinfunction "1_1") (pintype "passive"))
      (node (ref "C174") (pin "1") (pinfunction "1_1") (pintype "passive"))
      (node (ref "C175") (pin "1") (pinfunction "1_1") (pintype "passive"))
      (node (ref "C176") (pin "1") (pinfunction "1_1") (pintype "passive"))
      (node (ref "C177") (pin "1") (pinfunction "1_1") (pintype "passive"))
      (node (ref "C178") (pin "1") (pinfunction "1_1") (pintype "passive"))
      (node (ref "C179") (pin "1") (pinfunction "1_1") (pintype "passive"))
      (node (ref "C180") (pin "1") (pinfunction "1_1") (pintype "passive"))
      (node (ref "C181") (pin "1") (pinfunction "1_1") (pintype "passive"))
      (node (ref "C182") (pin "1") (pinfunction "1_1") (pintype "passive"))
      (node (ref "C183") (pin "1") (pinfunction "1_1") (pintype "passive"))
      (node (ref "C184") (pin "1") (pinfunction "1_1") (pintype "passive"))
      (node (ref "C185") (pin "1") (pinfunction "1_1") (pintype "passive"))
      (node (ref "C186") (pin "1") (pinfunction "1_1") (pintype "passive"))
      (node (ref "C187") (pin "1") (pinfunction "1_1") (pintype "passive"))
      (node (ref "C188") (pin "1") (pinfunction "1_1") (pintype "passive"))
      (node (ref "IC8") (pin "AA6") (pinfunction "VCCIO3_AA6") (pintype "power_in"))
      (node (ref "IC8") (pin "AB2") (pinfunction "VCCIO3_AB2") (pintype "power_in"))
      (node (ref "IC8") (pin "AB21") (pinfunction "VCCIO4_AB21") (pintype "power_in"))
      (node (ref "IC8") (pin "N4") (pinfunction "VCCIO2_N4") (pintype "power_in"))
      (node (ref "IC8") (pin "P18") (pinfunction "VCCIO5_P18") (pintype "power_in"))
      (node (ref "IC8") (pin "R4") (pinfunction "VCCIO2_R4") (pintype "power_in"))
      (node (ref "IC8") (pin "T19") (pinfunction "VCCIO5_T19") (pintype "power_in"))
      (node (ref "IC8") (pin "U4") (pinfunction "VCCIO2_U4") (pintype "power_in"))
      (node (ref "IC8") (pin "V19") (pinfunction "VCCIO5_V19") (pintype "power_in"))
      (node (ref "IC8") (pin "W11") (pinfunction "VCCIO3_W11") (pintype "power_in"))
      (node (ref "IC8") (pin "W12") (pinfunction "VCCIO4_W12") (pintype "power_in"))
      (node (ref "IC8") (pin "W16") (pinfunction "VCCIO4_W16") (pintype "power_in"))
      (node (ref "IC8") (pin "W18") (pinfunction "VCCIO4_W18") (pintype "power_in"))
      (node (ref "IC8") (pin "W4") (pinfunction "VCCIO2_W4") (pintype "power_in"))
      (node (ref "IC8") (pin "W5") (pinfunction "VCCIO3_W5") (pintype "power_in"))
      (node (ref "IC8") (pin "W9") (pinfunction "VCCIO3_W9") (pintype "power_in"))
      (node (ref "IC8") (pin "Y14") (pinfunction "VCCIO4_Y14") (pintype "power_in"))
      (node (ref "IC8") (pin "Y19") (pinfunction "VCCIO5_Y19") (pintype "power_in"))
    )
    (net (code "58") (name "VCC2P5") (class "Default")
      (node (ref "FR37") (pin "1") (pinfunction "1_1") (pintype "passive"))
    )
    (net (code "59") (name "VCC2P5A_FPGA") (class "Default")
      (node (ref "C132") (pin "2") (pinfunction "2_2") (pintype "passive"))
      (node (ref "C133") (pin "2") (pinfunction "2_2") (pintype "passive"))
      (node (ref "C134") (pin "2") (pinfunction "2_2") (pintype "passive"))
      (node (ref "C135") (pin "2") (pinfunction "2_2") (pintype "passive"))
      (node (ref "C136") (pin "1") (pinfunction "1_1") (pintype "passive"))
      (node (ref "C149") (pin "1") (pinfunction "1_1") (pintype "passive"))
      (node (ref "C150") (pin "1") (pinfunction "1_1") (pintype "passive"))
      (node (ref "C151") (pin "1") (pinfunction "1_1") (pintype "passive"))
      (node (ref "C152") (pin "1") (pinfunction "1_1") (pintype "passive"))
      (node (ref "FR37") (pin "2") (pinfunction "2_2") (pintype "passive"))
      (node (ref "IC8") (pin "F18") (pinfunction "VCCA2_F18") (pintype "power_in"))
      (node (ref "IC8") (pin "G6") (pinfunction "VCCA3_G6") (pintype "power_in"))
      (node (ref "IC8") (pin "T6") (pinfunction "VCCA1_T6") (pintype "power_in"))
      (node (ref "IC8") (pin "U18") (pinfunction "VCCA4_U18") (pintype "power_in"))
      (node (ref "J11") (pin "4") (pinfunction "4_4") (pintype "passive"))
      (node (ref "R52") (pin "1") (pinfunction "1_1") (pintype "passive"))
      (node (ref "R54") (pin "1") (pinfunction "1_1") (pintype "passive"))
      (node (ref "R55") (pin "2") (pinfunction "2_2") (pintype "passive"))
      (node (ref "R57") (pin "1") (pinfunction "1_1") (pintype "passive"))
      (node (ref "R58") (pin "2") (pinfunction "2_2") (pintype "passive"))
      (node (ref "R60") (pin "1") (pinfunction "1_1") (pintype "passive"))
    )
    (net (code "60") (name "VCC3P3") (class "Default")
      (node (ref "C125") (pin "1") (pinfunction "1_1") (pintype "passive"))
      (node (ref "C142") (pin "2") (pinfunction "2_2") (pintype "passive"))
      (node (ref "C143") (pin "2") (pinfunction "2_2") (pintype "passive"))
      (node (ref "C144") (pin "2") (pinfunction "2_2") (pintype "passive"))
      (node (ref "C145") (pin "2") (pinfunction "2_2") (pintype "passive"))
      (node (ref "C146") (pin "1") (pinfunction "1_1") (pintype "passive"))
      (node (ref "C147") (pin "1") (pinfunction "1_1") (pintype "passive"))
      (node (ref "C148") (pin "1") (pinfunction "1_1") (pintype "passive"))
      (node (ref "C167") (pin "1") (pinfunction "1_1") (pintype "passive"))
      (node (ref "C168") (pin "1") (pinfunction "1_1") (pintype "passive"))
      (node (ref "C169") (pin "1") (pinfunction "1_1") (pintype "passive"))
      (node (ref "C170") (pin "1") (pinfunction "1_1") (pintype "passive"))
      (node (ref "IC10") (pin "8") (pinfunction "VCC_8") (pintype "passive"))
      (node (ref "IC8") (pin "D4") (pinfunction "VCCIO1_D4") (pintype "power_in"))
      (node (ref "IC8") (pin "F4") (pinfunction "VCCIO1_F4") (pintype "power_in"))
      (node (ref "IC8") (pin "H4") (pinfunction "VCCIO1_H4") (pintype "power_in"))
      (node (ref "IC8") (pin "K4") (pinfunction "VCCIO1_K4") (pintype "power_in"))
      (node (ref "IC9") (pin "16") (pinfunction "V+_16") (pintype "passive"))
      (node (ref "J13") (pin "2") (pinfunction "2_2") (pintype "passive"))
      (node (ref "J14") (pin "2") (pinfunction "2_2") (pintype "passive"))
      (node (ref "R61") (pin "1") (pinfunction "1_1") (pintype "passive"))
      (node (ref "R66") (pin "1") (pinfunction "1_1") (pintype "passive"))
      (node (ref "R70") (pin "1") (pinfunction "1_1") (pintype "passive"))
      (node (ref "R71") (pin "1") (pinfunction "1_1") (pintype "passive"))
      (node (ref "R73") (pin "1") (pinfunction "1_1") (pintype "passive"))
    )
    (net (code "61") (name "VCC_INT") (class "Default")
      (node (ref "R63") (pin "1") (pinfunction "1_1") (pintype "passive"))
    )
    (net (code "62") (name "VDIO_LMS_FPGA") (class "Default")
      (node (ref "C137") (pin "2") (pinfunction "2_2") (pintype "passive"))
      (node (ref "C138") (pin "2") (pinfunction "2_2") (pintype "passive"))
      (node (ref "C139") (pin "2") (pinfunction "2_2") (pintype "passive"))
      (node (ref "C140") (pin "2") (pinfunction "2_2") (pintype "passive"))
      (node (ref "C141") (pin "1") (pinfunction "1_1") (pintype "passive"))
      (node (ref "C153") (pin "1") (pinfunction "1_1") (pintype "passive"))
      (node (ref "C154") (pin "1") (pinfunction "1_1") (pintype "passive"))
      (node (ref "C155") (pin "1") (pinfunction "1_1") (pintype "passive"))
      (node (ref "C156") (pin "1") (pinfunction "1_1") (pintype "passive"))
      (node (ref "C157") (pin "1") (pinfunction "1_1") (pintype "passive"))
      (node (ref "C158") (pin "1") (pinfunction "1_1") (pintype "passive"))
      (node (ref "C159") (pin "1") (pinfunction "1_1") (pintype "passive"))
      (node (ref "C160") (pin "1") (pinfunction "1_1") (pintype "passive"))
      (node (ref "C161") (pin "1") (pinfunction "1_1") (pintype "passive"))
      (node (ref "C162") (pin "1") (pinfunction "1_1") (pintype "passive"))
      (node (ref "C163") (pin "1") (pinfunction "1_1") (pintype "passive"))
      (node (ref "C164") (pin "1") (pinfunction "1_1") (pintype "passive"))
      (node (ref "C165") (pin "1") (pinfunction "1_1") (pintype "passive"))
      (node (ref "C166") (pin "1") (pinfunction "1_1") (pintype "passive"))
      (node (ref "IC8") (pin "A2") (pinfunction "VCCIO8_A2") (pintype "power_in"))
      (node (ref "IC8") (pin "A21") (pinfunction "VCCIO7_A21") (pintype "power_in"))
      (node (ref "IC8") (pin "D11") (pinfunction "VCCIO8_D11") (pintype "power_in"))
      (node (ref "IC8") (pin "D12") (pinfunction "VCCIO7_D12") (pintype "power_in"))
      (node (ref "IC8") (pin "D14") (pinfunction "VCCIO7_D14") (pintype "power_in"))
      (node (ref "IC8") (pin "D16") (pinfunction "VCCIO7_D16") (pintype "power_in"))
      (node (ref "IC8") (pin "D18") (pinfunction "VCCIO7_D18") (pintype "power_in"))
      (node (ref "IC8") (pin "D5") (pinfunction "VCCIO8_D5") (pintype "power_in"))
      (node (ref "IC8") (pin "D9") (pinfunction "VCCIO8_D9") (pintype "power_in"))
      (node (ref "IC8") (pin "E19") (pinfunction "VCCIO6_E19") (pintype "power_in"))
      (node (ref "IC8") (pin "E8") (pinfunction "VCCIO8_E8") (pintype "power_in"))
      (node (ref "IC8") (pin "G19") (pinfunction "VCCIO6_G19") (pintype "power_in"))
      (node (ref "IC8") (pin "J20") (pinfunction "VCCIO6_J20") (pintype "power_in"))
      (node (ref "IC8") (pin "L19") (pinfunction "VCCIO6_L19") (pintype "power_in"))
    )
    (net (code "63") (name "unconnected-(J11-Pad6)") (class "Default")
      (node (ref "J11") (pin "6") (pinfunction "6_6") (pintype "passive+no_connect"))
    )
    (net (code "64") (name "unconnected-(J11-Pad7)") (class "Default")
      (node (ref "J11") (pin "7") (pinfunction "7_7") (pintype "passive+no_connect"))
    )
    (net (code "65") (name "unconnected-(J11-Pad8)") (class "Default")
      (node (ref "J11") (pin "8") (pinfunction "8_8") (pintype "passive+no_connect"))
    )
  )
)
